# MPB-03a.net
KiCad netlist of a schematic drawn in EAGLE
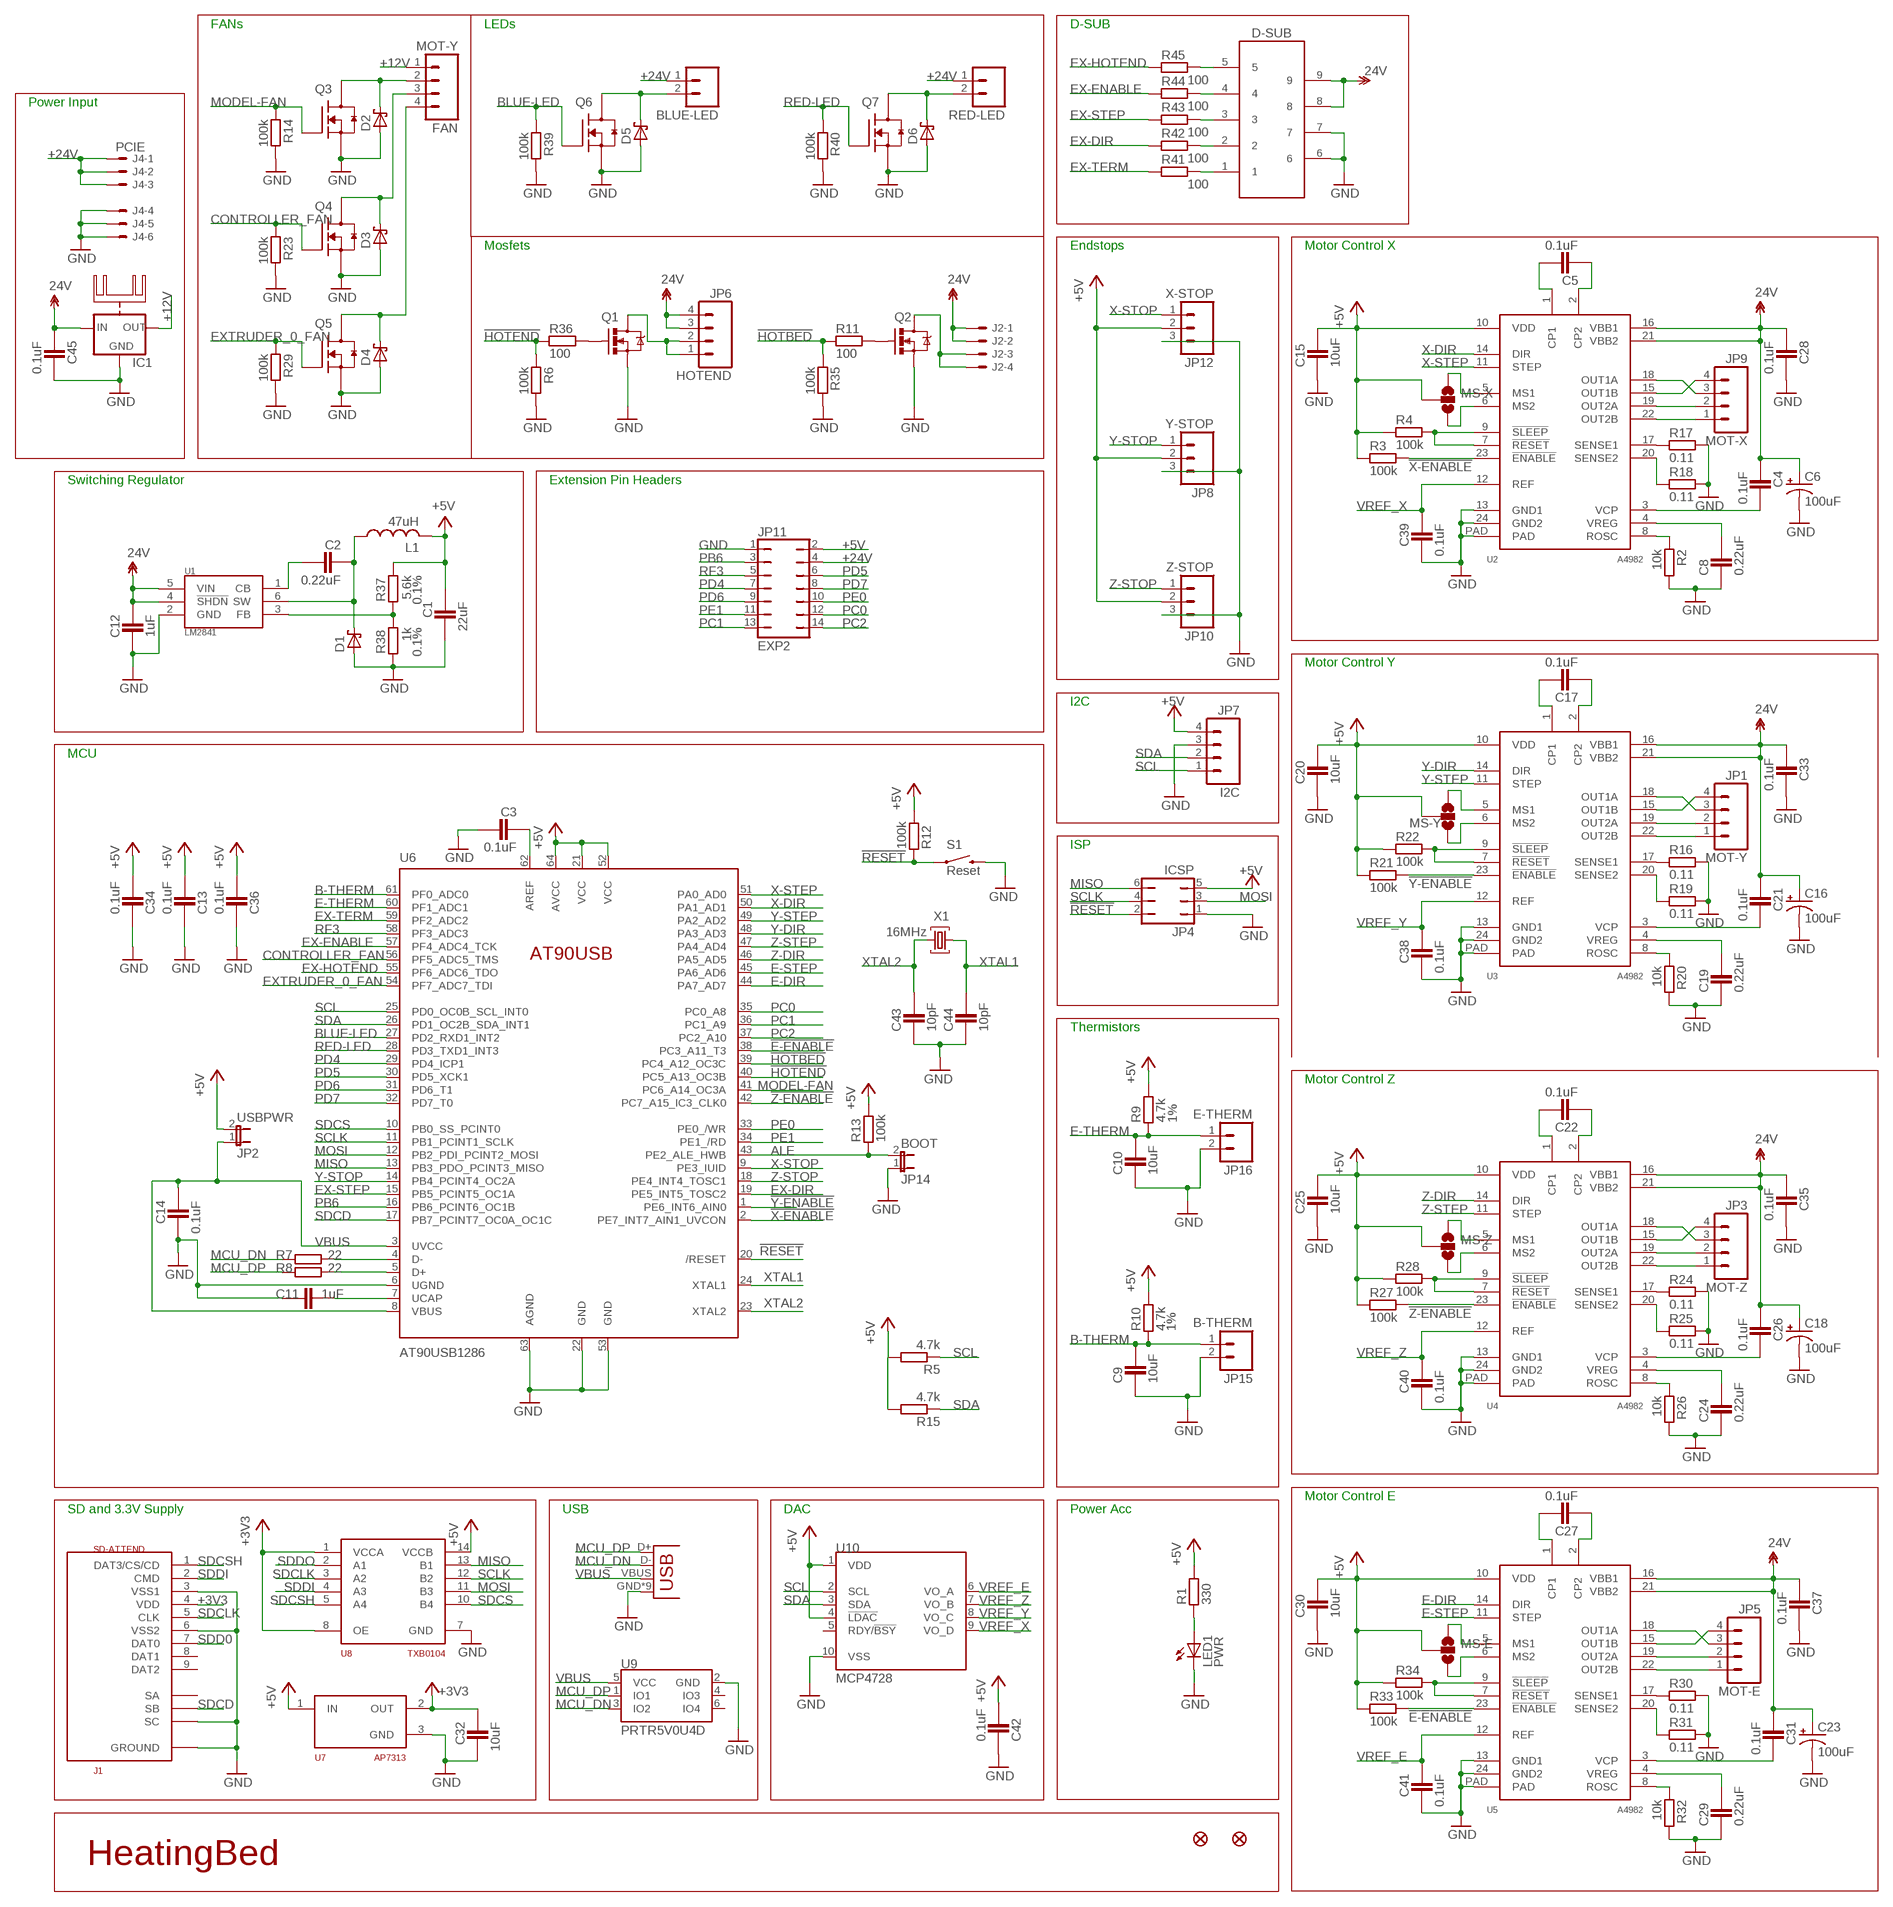
[diagram p0: schematic, sheet 1]

(export (version "E")
  (design (tool "Eeschema 10.0.6"))
  (components
    (comp (ref "BLUE-LED")
      (value "M02POLAR")
      (footprint "eagle-import:MOLEX-1X2")
      (libsource (lib "eagle-import") (part "M02POLAR"))
    )
    (comp (ref "C1")
      (value "22uF")
      (footprint "eagle-import:CAPC2012X145AN")
      (libsource (lib "eagle-import") (part "CAPACITOR_0805"))
    )
    (comp (ref "C2")
      (value "0.22uF")
      (footprint "eagle-import:CAPC2012X145AN")
      (libsource (lib "eagle-import") (part "CAPACITOR_0805"))
    )
    (comp (ref "C3")
      (value "0.1uF")
      (footprint "eagle-import:CAPC2012X145AN")
      (libsource (lib "eagle-import") (part "CAPACITOR_0805"))
    )
    (comp (ref "C4")
      (value "0.1uF")
      (footprint "eagle-import:CAPC2012X145AN")
      (libsource (lib "eagle-import") (part "CAPACITOR_0805"))
    )
    (comp (ref "C5")
      (value "0.1uF")
      (footprint "eagle-import:CAPC2012X145AN")
      (libsource (lib "eagle-import") (part "CAPACITOR_0805"))
    )
    (comp (ref "C6")
      (value "100uF")
      (footprint "eagle-import:PANASONIC_D")
      (libsource (lib "eagle-import") (part "CPOL-USD"))
    )
    (comp (ref "C8")
      (value "0.22uF")
      (footprint "eagle-import:CAPC2012X145AN")
      (libsource (lib "eagle-import") (part "CAPACITOR_0805"))
    )
    (comp (ref "C9")
      (value "10uF")
      (footprint "eagle-import:CAPC2012X145AN")
      (libsource (lib "eagle-import") (part "CAPACITOR_0805"))
    )
    (comp (ref "C10")
      (value "10uF")
      (footprint "eagle-import:CAPC2012X145AN")
      (libsource (lib "eagle-import") (part "CAPACITOR_0805"))
    )
    (comp (ref "C11")
      (value "1uF")
      (footprint "eagle-import:CAPC2012X145AN")
      (libsource (lib "eagle-import") (part "CAPACITOR_0805"))
    )
    (comp (ref "C12")
      (value "1uF")
      (footprint "eagle-import:CAPC2012X145AN")
      (libsource (lib "eagle-import") (part "CAPACITOR_0805"))
    )
    (comp (ref "C13")
      (value "0.1uF")
      (footprint "eagle-import:CAPC2012X145AN")
      (libsource (lib "eagle-import") (part "CAPACITOR_0805"))
    )
    (comp (ref "C14")
      (value "0.1uF")
      (footprint "eagle-import:CAPC2012X145AN")
      (libsource (lib "eagle-import") (part "CAPACITOR_0805"))
    )
    (comp (ref "C15")
      (value "10uF")
      (footprint "eagle-import:CAPC2012X145AN")
      (libsource (lib "eagle-import") (part "CAPACITOR_0805"))
    )
    (comp (ref "C16")
      (value "100uF")
      (footprint "eagle-import:PANASONIC_D")
      (libsource (lib "eagle-import") (part "CPOL-USD"))
    )
    (comp (ref "C17")
      (value "0.1uF")
      (footprint "eagle-import:CAPC2012X145AN")
      (libsource (lib "eagle-import") (part "CAPACITOR_0805"))
    )
    (comp (ref "C18")
      (value "100uF")
      (footprint "eagle-import:PANASONIC_D")
      (libsource (lib "eagle-import") (part "CPOL-USD"))
    )
    (comp (ref "C19")
      (value "0.22uF")
      (footprint "eagle-import:CAPC2012X145AN")
      (libsource (lib "eagle-import") (part "CAPACITOR_0805"))
    )
    (comp (ref "C20")
      (value "10uF")
      (footprint "eagle-import:CAPC2012X145AN")
      (libsource (lib "eagle-import") (part "CAPACITOR_0805"))
    )
    (comp (ref "C21")
      (value "0.1uF")
      (footprint "eagle-import:CAPC2012X145AN")
      (libsource (lib "eagle-import") (part "CAPACITOR_0805"))
    )
    (comp (ref "C22")
      (value "0.1uF")
      (footprint "eagle-import:CAPC2012X145AN")
      (libsource (lib "eagle-import") (part "CAPACITOR_0805"))
    )
    (comp (ref "C23")
      (value "100uF")
      (footprint "eagle-import:PANASONIC_D")
      (libsource (lib "eagle-import") (part "CPOL-USD"))
    )
    (comp (ref "C24")
      (value "0.22uF")
      (footprint "eagle-import:CAPC2012X145AN")
      (libsource (lib "eagle-import") (part "CAPACITOR_0805"))
    )
    (comp (ref "C25")
      (value "10uF")
      (footprint "eagle-import:CAPC2012X145AN")
      (libsource (lib "eagle-import") (part "CAPACITOR_0805"))
    )
    (comp (ref "C26")
      (value "0.1uF")
      (footprint "eagle-import:CAPC2012X145AN")
      (libsource (lib "eagle-import") (part "CAPACITOR_0805"))
    )
    (comp (ref "C27")
      (value "0.1uF")
      (footprint "eagle-import:CAPC2012X145AN")
      (libsource (lib "eagle-import") (part "CAPACITOR_0805"))
    )
    (comp (ref "C28")
      (value "0.1uF")
      (footprint "eagle-import:CAPC2012X145AN")
      (libsource (lib "eagle-import") (part "CAPACITOR_0805"))
    )
    (comp (ref "C29")
      (value "0.22uF")
      (footprint "eagle-import:CAPC2012X145AN")
      (libsource (lib "eagle-import") (part "CAPACITOR_0805"))
    )
    (comp (ref "C30")
      (value "10uF")
      (footprint "eagle-import:CAPC2012X145AN")
      (libsource (lib "eagle-import") (part "CAPACITOR_0805"))
    )
    (comp (ref "C31")
      (value "0.1uF")
      (footprint "eagle-import:CAPC2012X145AN")
      (libsource (lib "eagle-import") (part "CAPACITOR_0805"))
    )
    (comp (ref "C32")
      (value "10uF")
      (footprint "eagle-import:CAPC2012X145AN")
      (libsource (lib "eagle-import") (part "CAPACITOR_0805"))
    )
    (comp (ref "C33")
      (value "0.1uF")
      (footprint "eagle-import:CAPC2012X145AN")
      (libsource (lib "eagle-import") (part "CAPACITOR_0805"))
    )
    (comp (ref "C34")
      (value "0.1uF")
      (footprint "eagle-import:CAPC2012X145AN")
      (libsource (lib "eagle-import") (part "CAPACITOR_0805"))
    )
    (comp (ref "C35")
      (value "0.1uF")
      (footprint "eagle-import:CAPC2012X145AN")
      (libsource (lib "eagle-import") (part "CAPACITOR_0805"))
    )
    (comp (ref "C36")
      (value "0.1uF")
      (footprint "eagle-import:CAPC2012X145AN")
      (libsource (lib "eagle-import") (part "CAPACITOR_0805"))
    )
    (comp (ref "C37")
      (value "0.1uF")
      (footprint "eagle-import:CAPC2012X145AN")
      (libsource (lib "eagle-import") (part "CAPACITOR_0805"))
    )
    (comp (ref "C38")
      (value "0.1uF")
      (footprint "eagle-import:CAPC2012X145AN")
      (libsource (lib "eagle-import") (part "CAPACITOR_0805"))
    )
    (comp (ref "C39")
      (value "0.1uF")
      (footprint "eagle-import:CAPC2012X145AN")
      (libsource (lib "eagle-import") (part "CAPACITOR_0805"))
    )
    (comp (ref "C40")
      (value "0.1uF")
      (footprint "eagle-import:CAPC2012X145AN")
      (libsource (lib "eagle-import") (part "CAPACITOR_0805"))
    )
    (comp (ref "C41")
      (value "0.1uF")
      (footprint "eagle-import:CAPC2012X145AN")
      (libsource (lib "eagle-import") (part "CAPACITOR_0805"))
    )
    (comp (ref "C42")
      (value "0.1uF")
      (footprint "eagle-import:CAPC2012X145AN")
      (libsource (lib "eagle-import") (part "CAPACITOR_0805"))
    )
    (comp (ref "C43")
      (value "10pF")
      (footprint "eagle-import:CAPC2012X145AN")
      (libsource (lib "eagle-import") (part "CAPACITOR_0805"))
    )
    (comp (ref "C44")
      (value "10pF")
      (footprint "eagle-import:CAPC2012X145AN")
      (libsource (lib "eagle-import") (part "CAPACITOR_0805"))
    )
    (comp (ref "C45")
      (value "0.1uF")
      (footprint "eagle-import:CAPC2012X145AN")
      (libsource (lib "eagle-import") (part "CAPACITOR_0805"))
    )
    (comp (ref "D-SUB")
      (value "618009211721")
      (footprint "eagle-import:618009211721")
      (libsource (lib "eagle-import") (part "618009211721"))
    )
    (comp (ref "D1")
      (value "SCH-DIODESMA")
      (footprint "eagle-import:SMA")
      (libsource (lib "eagle-import") (part "SCH-DIODESMA"))
    )
    (comp (ref "D2")
      (value "SCH-DIODESMA")
      (footprint "eagle-import:SMA")
      (libsource (lib "eagle-import") (part "SCH-DIODESMA"))
    )
    (comp (ref "D3")
      (value "SCH-DIODESMA")
      (footprint "eagle-import:SMA")
      (libsource (lib "eagle-import") (part "SCH-DIODESMA"))
    )
    (comp (ref "D4")
      (value "SCH-DIODESMA")
      (footprint "eagle-import:SMA")
      (libsource (lib "eagle-import") (part "SCH-DIODESMA"))
    )
    (comp (ref "D5")
      (value "SCH-DIODESMA")
      (footprint "eagle-import:SMA")
      (libsource (lib "eagle-import") (part "SCH-DIODESMA"))
    )
    (comp (ref "D6")
      (value "SCH-DIODESMA")
      (footprint "eagle-import:SMA")
      (libsource (lib "eagle-import") (part "SCH-DIODESMA"))
    )
    (comp (ref "FAN")
      (value "MOT-Y")
      (footprint "eagle-import:MOLEX-1X4")
      (libsource (lib "eagle-import") (part "M04POLAR"))
    )
    (comp (ref "IC1")
      (value "78XXH")
      (footprint "eagle-import:TO220-15X17X25")
      (libsource (lib "eagle-import") (part "78XXH"))
    )
    (comp (ref "J1")
      (value "SD-ATTEND")
      (footprint "eagle-import:SD-ATTEND")
      (libsource (lib "eagle-import") (part "SD-ATTEND"))
    )
    (comp (ref "J2")
      (value "5566-4")
      (footprint "eagle-import:5566-4")
      (libsource (lib "eagle-import") (part "5566-4"))
    )
    (comp (ref "J3")
      (value "USB-MICRO-PTH")
      (footprint "eagle-import:USB-MICROB-PTH")
      (libsource (lib "eagle-import") (part "USB-MICRO-PTH"))
    )
    (comp (ref "J4")
      (value "PCIE")
      (footprint "eagle-import:5566-6")
      (fields (field (name "MPN") "95566-61002"))
      (libsource (lib "eagle-import") (part "5566-6"))
    )
    (comp (ref "JP1")
      (value "MOT-Y")
      (footprint "eagle-import:MOLEX-1X4")
      (libsource (lib "eagle-import") (part "M04POLAR"))
    )
    (comp (ref "JP2")
      (value "USBPWR")
      (footprint "eagle-import:1X02")
      (libsource (lib "eagle-import") (part "JUMPER-2PTH"))
    )
    (comp (ref "JP3")
      (value "MOT-Z")
      (footprint "eagle-import:MOLEX-1X4")
      (libsource (lib "eagle-import") (part "M04POLAR"))
    )
    (comp (ref "JP4")
      (value "ICSP")
      (footprint "eagle-import:JP3Q")
      (libsource (lib "eagle-import") (part "JP3Q"))
    )
    (comp (ref "JP5")
      (value "MOT-E")
      (footprint "eagle-import:MOLEX-1X4")
      (libsource (lib "eagle-import") (part "M04POLAR"))
    )
    (comp (ref "JP6")
      (value "HOTEND")
      (footprint "eagle-import:MOLEX-1X4")
      (libsource (lib "eagle-import") (part "M04POLAR"))
    )
    (comp (ref "JP7")
      (value "I2C")
      (footprint "eagle-import:MOLEX-1X4")
      (libsource (lib "eagle-import") (part "M04POLAR"))
    )
    (comp (ref "JP8")
      (value "Y-STOP")
      (footprint "eagle-import:MOLEX-1X3")
      (libsource (lib "eagle-import") (part "M03POLAR"))
    )
    (comp (ref "JP9")
      (value "MOT-X")
      (footprint "eagle-import:MOLEX-1X4")
      (libsource (lib "eagle-import") (part "M04POLAR"))
    )
    (comp (ref "JP10")
      (value "Z-STOP")
      (footprint "eagle-import:MOLEX-1X3")
      (libsource (lib "eagle-import") (part "M03POLAR"))
    )
    (comp (ref "JP11")
      (value "EXP2")
      (footprint "eagle-import:JP7Q")
      (libsource (lib "eagle-import") (part "JP7Q"))
    )
    (comp (ref "JP12")
      (value "X-STOP")
      (footprint "eagle-import:MOLEX-1X3")
      (libsource (lib "eagle-import") (part "M03POLAR"))
    )
    (comp (ref "JP14")
      (value "BOOT")
      (footprint "eagle-import:1X02")
      (libsource (lib "eagle-import") (part "JUMPER-2PTH"))
    )
    (comp (ref "JP15")
      (value "B-THERM")
      (footprint "eagle-import:1X02")
      (libsource (lib "eagle-import") (part "M02PTH"))
    )
    (comp (ref "JP16")
      (value "E-THERM")
      (footprint "eagle-import:1X02")
      (libsource (lib "eagle-import") (part "M02PTH"))
    )
    (comp (ref "JP26")
      (value "FIDUCIAL1X2.5")
      (footprint "eagle-import:FIDUCIAL-1X2.5")
      (libsource (lib "eagle-import") (part "FIDUCIAL1X2.5"))
    )
    (comp (ref "JP33")
      (value "FIDUCIAL1X2.5")
      (footprint "eagle-import:FIDUCIAL-1X2.5")
      (libsource (lib "eagle-import") (part "FIDUCIAL1X2.5"))
    )
    (comp (ref "L1")
      (value "47uH")
      (footprint "eagle-import:SDR1006")
      (libsource (lib "eagle-import") (part "L-US"))
    )
    (comp (ref "LED1")
      (value "PWR")
      (footprint "eagle-import:CHIP-LED0805")
      (libsource (lib "eagle-import") (part "LEDCHIP-LED0805"))
    )
    (comp (ref "MS-E")
      (value "SOLDERJUMPER_2WAYCONNECTED")
      (footprint "eagle-import:SJ_3_CONNECTED")
      (libsource (lib "eagle-import") (part "SOLDERJUMPER_2WAYCONNECTED"))
    )
    (comp (ref "MS-X")
      (value "SOLDERJUMPER_2WAYCONNECTED")
      (footprint "eagle-import:SJ_3_CONNECTED")
      (libsource (lib "eagle-import") (part "SOLDERJUMPER_2WAYCONNECTED"))
    )
    (comp (ref "MS-Y")
      (value "SOLDERJUMPER_2WAYCONNECTED")
      (footprint "eagle-import:SJ_3_CONNECTED")
      (libsource (lib "eagle-import") (part "SOLDERJUMPER_2WAYCONNECTED"))
    )
    (comp (ref "MS-Z")
      (value "SOLDERJUMPER_2WAYCONNECTED")
      (footprint "eagle-import:SJ_3_CONNECTED")
      (libsource (lib "eagle-import") (part "SOLDERJUMPER_2WAYCONNECTED"))
    )
    (comp (ref "Q1")
      (value "RFP30N06LE")
      (footprint "eagle-import:TO220V")
      (libsource (lib "eagle-import") (part "MOSFET-NCHANNELPTH2"))
    )
    (comp (ref "Q2")
      (value "RFP30N06LE")
      (footprint "eagle-import:TO220V")
      (libsource (lib "eagle-import") (part "MOSFET-NCHANNELPTH2"))
    )
    (comp (ref "Q3")
      (value "RFP30N06LE")
      (footprint "eagle-import:SOT95P280X135-3N")
      (libsource (lib "eagle-import") (part "MOSFET-NCH_SOT-23"))
    )
    (comp (ref "Q4")
      (value "RFP30N06LE")
      (footprint "eagle-import:SOT95P280X135-3N")
      (libsource (lib "eagle-import") (part "MOSFET-NCH_SOT-23"))
    )
    (comp (ref "Q5")
      (value "RFP30N06LE")
      (footprint "eagle-import:SOT95P280X135-3N")
      (libsource (lib "eagle-import") (part "MOSFET-NCH_SOT-23"))
    )
    (comp (ref "Q6")
      (value "RFP30N06LE")
      (footprint "eagle-import:SOT95P280X135-3N")
      (libsource (lib "eagle-import") (part "MOSFET-NCH_SOT-23"))
    )
    (comp (ref "Q7")
      (value "RFP30N06LE")
      (footprint "eagle-import:SOT95P280X135-3N")
      (libsource (lib "eagle-import") (part "MOSFET-NCH_SOT-23"))
    )
    (comp (ref "R1")
      (value "330")
      (footprint "eagle-import:RESC2012X70N")
      (libsource (lib "eagle-import") (part "RESISTOR_0805"))
    )
    (comp (ref "R2")
      (value "10k")
      (footprint "eagle-import:RESC2012X70N")
      (libsource (lib "eagle-import") (part "RESISTOR_0805"))
    )
    (comp (ref "R3")
      (value "100k")
      (footprint "eagle-import:RESC2012X70N")
      (libsource (lib "eagle-import") (part "RESISTOR_0805"))
    )
    (comp (ref "R4")
      (value "100k")
      (footprint "eagle-import:RESC2012X70N")
      (libsource (lib "eagle-import") (part "RESISTOR_0805"))
    )
    (comp (ref "R5")
      (value "4.7k")
      (footprint "eagle-import:RESC2012X70N")
      (libsource (lib "eagle-import") (part "RESISTOR_0805"))
    )
    (comp (ref "R6")
      (value "100k")
      (footprint "eagle-import:RESC2012X70N")
      (libsource (lib "eagle-import") (part "RESISTOR_0805"))
    )
    (comp (ref "R7")
      (value "22")
      (footprint "eagle-import:RESC2012X70N")
      (libsource (lib "eagle-import") (part "RESISTOR_0805"))
    )
    (comp (ref "R8")
      (value "22")
      (footprint "eagle-import:RESC2012X70N")
      (libsource (lib "eagle-import") (part "RESISTOR_0805"))
    )
    (comp (ref "R9")
      (value "4.7k")
      (footprint "eagle-import:RESC2012X70N")
      (fields (field (name "TOLERANCE") "1%"))
      (libsource (lib "eagle-import") (part "RESISTOR_0805"))
    )
    (comp (ref "R10")
      (value "4.7k")
      (footprint "eagle-import:RESC2012X70N")
      (fields (field (name "TOLERANCE") "1%"))
      (libsource (lib "eagle-import") (part "RESISTOR_0805"))
    )
    (comp (ref "R11")
      (value "100")
      (footprint "eagle-import:RESC2012X70N")
      (libsource (lib "eagle-import") (part "RESISTOR_0805"))
    )
    (comp (ref "R12")
      (value "100k")
      (footprint "eagle-import:RESC2012X70N")
      (libsource (lib "eagle-import") (part "RESISTOR_0805"))
    )
    (comp (ref "R13")
      (value "100k")
      (footprint "eagle-import:RESC2012X70N")
      (libsource (lib "eagle-import") (part "RESISTOR_0805"))
    )
    (comp (ref "R14")
      (value "100k")
      (footprint "eagle-import:RESC2012X70N")
      (libsource (lib "eagle-import") (part "RESISTOR_0805"))
    )
    (comp (ref "R15")
      (value "4.7k")
      (footprint "eagle-import:RESC2012X70N")
      (libsource (lib "eagle-import") (part "RESISTOR_0805"))
    )
    (comp (ref "R16")
      (value "0.11")
      (footprint "eagle-import:RESC2012X70N")
      (libsource (lib "eagle-import") (part "RESISTOR_0805"))
    )
    (comp (ref "R17")
      (value "0.11")
      (footprint "eagle-import:RESC2012X70N")
      (libsource (lib "eagle-import") (part "RESISTOR_0805"))
    )
    (comp (ref "R18")
      (value "0.11")
      (footprint "eagle-import:RESC2012X70N")
      (libsource (lib "eagle-import") (part "RESISTOR_0805"))
    )
    (comp (ref "R19")
      (value "0.11")
      (footprint "eagle-import:RESC2012X70N")
      (libsource (lib "eagle-import") (part "RESISTOR_0805"))
    )
    (comp (ref "R20")
      (value "10k")
      (footprint "eagle-import:RESC2012X70N")
      (libsource (lib "eagle-import") (part "RESISTOR_0805"))
    )
    (comp (ref "R21")
      (value "100k")
      (footprint "eagle-import:RESC2012X70N")
      (libsource (lib "eagle-import") (part "RESISTOR_0805"))
    )
    (comp (ref "R22")
      (value "100k")
      (footprint "eagle-import:RESC2012X70N")
      (libsource (lib "eagle-import") (part "RESISTOR_0805"))
    )
    (comp (ref "R23")
      (value "100k")
      (footprint "eagle-import:RESC2012X70N")
      (libsource (lib "eagle-import") (part "RESISTOR_0805"))
    )
    (comp (ref "R24")
      (value "0.11")
      (footprint "eagle-import:RESC2012X70N")
      (libsource (lib "eagle-import") (part "RESISTOR_0805"))
    )
    (comp (ref "R25")
      (value "0.11")
      (footprint "eagle-import:RESC2012X70N")
      (libsource (lib "eagle-import") (part "RESISTOR_0805"))
    )
    (comp (ref "R26")
      (value "10k")
      (footprint "eagle-import:RESC2012X70N")
      (libsource (lib "eagle-import") (part "RESISTOR_0805"))
    )
    (comp (ref "R27")
      (value "100k")
      (footprint "eagle-import:RESC2012X70N")
      (libsource (lib "eagle-import") (part "RESISTOR_0805"))
    )
    (comp (ref "R28")
      (value "100k")
      (footprint "eagle-import:RESC2012X70N")
      (libsource (lib "eagle-import") (part "RESISTOR_0805"))
    )
    (comp (ref "R29")
      (value "100k")
      (footprint "eagle-import:RESC2012X70N")
      (libsource (lib "eagle-import") (part "RESISTOR_0805"))
    )
    (comp (ref "R30")
      (value "0.11")
      (footprint "eagle-import:RESC2012X70N")
      (libsource (lib "eagle-import") (part "RESISTOR_0805"))
    )
    (comp (ref "R31")
      (value "0.11")
      (footprint "eagle-import:RESC2012X70N")
      (libsource (lib "eagle-import") (part "RESISTOR_0805"))
    )
    (comp (ref "R32")
      (value "10k")
      (footprint "eagle-import:RESC2012X70N")
      (libsource (lib "eagle-import") (part "RESISTOR_0805"))
    )
    (comp (ref "R33")
      (value "100k")
      (footprint "eagle-import:RESC2012X70N")
      (libsource (lib "eagle-import") (part "RESISTOR_0805"))
    )
    (comp (ref "R34")
      (value "100k")
      (footprint "eagle-import:RESC2012X70N")
      (libsource (lib "eagle-import") (part "RESISTOR_0805"))
    )
    (comp (ref "R35")
      (value "100k")
      (footprint "eagle-import:RESC2012X70N")
      (libsource (lib "eagle-import") (part "RESISTOR_0805"))
    )
    (comp (ref "R36")
      (value "100")
      (footprint "eagle-import:RESC2012X70N")
      (libsource (lib "eagle-import") (part "RESISTOR_0805"))
    )
    (comp (ref "R37")
      (value "5.6k")
      (footprint "eagle-import:RESC2012X70N")
      (fields (field (name "TOLERANCE") "0.1%"))
      (libsource (lib "eagle-import") (part "RESISTOR_0805"))
    )
    (comp (ref "R38")
      (value "1k")
      (footprint "eagle-import:RESC2012X70N")
      (fields (field (name "TOLERANCE") "0.1%"))
      (libsource (lib "eagle-import") (part "RESISTOR_0805"))
    )
    (comp (ref "R39")
      (value "100k")
      (footprint "eagle-import:RESC2012X70N")
      (libsource (lib "eagle-import") (part "RESISTOR_0805"))
    )
    (comp (ref "R40")
      (value "100k")
      (footprint "eagle-import:RESC2012X70N")
      (libsource (lib "eagle-import") (part "RESISTOR_0805"))
    )
    (comp (ref "R41")
      (value "100")
      (footprint "eagle-import:RESC2012X70N")
      (libsource (lib "eagle-import") (part "RESISTOR_0805"))
    )
    (comp (ref "R42")
      (value "100")
      (footprint "eagle-import:RESC2012X70N")
      (libsource (lib "eagle-import") (part "RESISTOR_0805"))
    )
    (comp (ref "R43")
      (value "100")
      (footprint "eagle-import:RESC2012X70N")
      (libsource (lib "eagle-import") (part "RESISTOR_0805"))
    )
    (comp (ref "R44")
      (value "100")
      (footprint "eagle-import:RESC2012X70N")
      (libsource (lib "eagle-import") (part "RESISTOR_0805"))
    )
    (comp (ref "R45")
      (value "100")
      (footprint "eagle-import:RESC2012X70N")
      (libsource (lib "eagle-import") (part "RESISTOR_0805"))
    )
    (comp (ref "RED-LED")
      (value "M02POLAR")
      (footprint "eagle-import:MOLEX-1X2")
      (libsource (lib "eagle-import") (part "M02POLAR"))
    )
    (comp (ref "S1")
      (value "Reset")
      (footprint "eagle-import:TACTILE_SWITCH_TALL")
      (libsource (lib "eagle-import") (part "SWITCH-MOMENTARY-2"))
    )
    (comp (ref "U1")
      (value "LM2841")
      (footprint "eagle-import:TSOT6")
      (libsource (lib "eagle-import") (part "LM2841"))
    )
    (comp (ref "U2")
      (value "A4982")
      (footprint "eagle-import:TSSOP-24")
      (libsource (lib "eagle-import") (part "A4982"))
    )
    (comp (ref "U3")
      (value "A4982")
      (footprint "eagle-import:TSSOP-24")
      (libsource (lib "eagle-import") (part "A4982"))
    )
    (comp (ref "U4")
      (value "A4982")
      (footprint "eagle-import:TSSOP-24")
      (libsource (lib "eagle-import") (part "A4982"))
    )
    (comp (ref "U5")
      (value "A4982")
      (footprint "eagle-import:TSSOP-24")
      (libsource (lib "eagle-import") (part "A4982"))
    )
    (comp (ref "U6")
      (value "AT90USB1286")
      (footprint "eagle-import:TQFP64-2")
      (libsource (lib "eagle-import") (part "AT90USB"))
    )
    (comp (ref "U7")
      (value "AP7313")
      (footprint "eagle-import:SOT23C")
      (libsource (lib "eagle-import") (part "AP7313"))
    )
    (comp (ref "U8")
      (value "TXB0104")
      (footprint "eagle-import:TSSOP14")
      (libsource (lib "eagle-import") (part "TXB0104"))
    )
    (comp (ref "U9")
      (value "PRTR5V0U4D")
      (footprint "eagle-import:SOT23-6")
      (libsource (lib "eagle-import") (part "PRTR5V0U4D"))
    )
    (comp (ref "U10")
      (value "MCP4728")
      (footprint "eagle-import:MSOP10")
      (libsource (lib "eagle-import") (part "MCP4728"))
    )
    (comp (ref "X1")
      (value "16MHz")
      (footprint "eagle-import:NDK-XTAL")
      (libsource (lib "eagle-import") (part "XTAL"))
    )
  )
  (nets
    (net (code "1") (name "+3V3") (class "Default")
      (node (ref "C32") (pin "1") (pinfunction "1_1") (pintype "passive"))
      (node (ref "J1") (pin "4") (pinfunction "VDD_4") (pintype "power_in"))
      (node (ref "U7") (pin "2") (pinfunction "OUT_2") (pintype "power_in"))
      (node (ref "U8") (pin "1") (pinfunction "VCCA_1") (pintype "power_in"))
      (node (ref "U8") (pin "8") (pinfunction "OE_8") (pintype "input"))
    )
    (net (code "2") (name "+5V") (class "Default")
      (node (ref "C1") (pin "1") (pinfunction "1_1") (pintype "passive"))
      (node (ref "C13") (pin "2") (pinfunction "2_2") (pintype "passive"))
      (node (ref "C15") (pin "2") (pinfunction "2_2") (pintype "passive"))
      (node (ref "C20") (pin "2") (pinfunction "2_2") (pintype "passive"))
      (node (ref "C25") (pin "2") (pinfunction "2_2") (pintype "passive"))
      (node (ref "C30") (pin "2") (pinfunction "2_2") (pintype "passive"))
      (node (ref "C34") (pin "2") (pinfunction "2_2") (pintype "passive"))
      (node (ref "C36") (pin "2") (pinfunction "2_2") (pintype "passive"))
      (node (ref "C42") (pin "2") (pinfunction "2_2") (pintype "passive"))
      (node (ref "JP10") (pin "2") (pinfunction "2_2") (pintype "passive"))
      (node (ref "JP11") (pin "2") (pinfunction "2_2") (pintype "passive"))
      (node (ref "JP12") (pin "2") (pinfunction "2_2") (pintype "passive"))
      (node (ref "JP2") (pin "2") (pinfunction "2_2") (pintype "passive"))
      (node (ref "JP4") (pin "5") (pinfunction "5_5") (pintype "passive"))
      (node (ref "JP7") (pin "4") (pinfunction "4_4") (pintype "passive"))
      (node (ref "JP8") (pin "2") (pinfunction "2_2") (pintype "passive"))
      (node (ref "L1") (pin "P$2") (pinfunction "2_P$2") (pintype "passive"))
      (node (ref "MS-E") (pin "2") (pinfunction "2_2") (pintype "passive"))
      (node (ref "MS-X") (pin "2") (pinfunction "2_2") (pintype "passive"))
      (node (ref "MS-Y") (pin "2") (pinfunction "2_2") (pintype "passive"))
      (node (ref "MS-Z") (pin "2") (pinfunction "2_2") (pintype "passive"))
      (node (ref "R1") (pin "2") (pinfunction "2_2") (pintype "passive"))
      (node (ref "R10") (pin "2") (pinfunction "2_2") (pintype "passive"))
      (node (ref "R12") (pin "2") (pinfunction "2_2") (pintype "passive"))
      (node (ref "R13") (pin "2") (pinfunction "2_2") (pintype "passive"))
      (node (ref "R15") (pin "2") (pinfunction "2_2") (pintype "passive"))
      (node (ref "R21") (pin "1") (pinfunction "1_1") (pintype "passive"))
      (node (ref "R22") (pin "1") (pinfunction "1_1") (pintype "passive"))
      (node (ref "R27") (pin "1") (pinfunction "1_1") (pintype "passive"))
      (node (ref "R28") (pin "1") (pinfunction "1_1") (pintype "passive"))
      (node (ref "R3") (pin "1") (pinfunction "1_1") (pintype "passive"))
      (node (ref "R33") (pin "1") (pinfunction "1_1") (pintype "passive"))
      (node (ref "R34") (pin "1") (pinfunction "1_1") (pintype "passive"))
      (node (ref "R37") (pin "1") (pinfunction "1_1") (pintype "passive"))
      (node (ref "R4") (pin "1") (pinfunction "1_1") (pintype "passive"))
      (node (ref "R5") (pin "2") (pinfunction "2_2") (pintype "passive"))
      (node (ref "R9") (pin "2") (pinfunction "2_2") (pintype "passive"))
      (node (ref "U10") (pin "1") (pinfunction "VDD_1") (pintype "power_in"))
      (node (ref "U10") (pin "4") (pinfunction "~{LDAC}_4") (pintype "input"))
      (node (ref "U2") (pin "10") (pinfunction "VDD_10") (pintype "power_in"))
      (node (ref "U3") (pin "10") (pinfunction "VDD_10") (pintype "power_in"))
      (node (ref "U4") (pin "10") (pinfunction "VDD_10") (pintype "power_in"))
      (node (ref "U5") (pin "10") (pinfunction "VDD_10") (pintype "power_in"))
      (node (ref "U6") (pin "21") (pinfunction "VCC_21") (pintype "power_in"))
      (node (ref "U6") (pin "52") (pinfunction "VCC_52") (pintype "power_in"))
      (node (ref "U6") (pin "64") (pinfunction "AVCC_64") (pintype "power_in"))
      (node (ref "U7") (pin "1") (pinfunction "IN_1") (pintype "power_in"))
      (node (ref "U8") (pin "14") (pinfunction "VCCB_14") (pintype "power_in"))
    )
    (net (code "3") (name "/+12V") (class "Default")
      (node (ref "FAN") (pin "1") (pinfunction "1_1") (pintype "passive"))
      (node (ref "IC1") (pin "OUT") (pinfunction "OUT_OUT") (pintype "passive"))
    )
    (net (code "4") (name "/ALE") (class "Default")
      (node (ref "JP14") (pin "2") (pinfunction "2_2") (pintype "passive"))
      (node (ref "R13") (pin "1") (pinfunction "1_1") (pintype "passive"))
      (node (ref "U6") (pin "43") (pinfunction "PE2_ALE_HWB_43") (pintype "bidirectional"))
    )
    (net (code "5") (name "/B-THERM") (class "Default")
      (node (ref "C9") (pin "2") (pinfunction "2_2") (pintype "passive"))
      (node (ref "JP15") (pin "1") (pinfunction "1_1") (pintype "passive"))
      (node (ref "R10") (pin "1") (pinfunction "1_1") (pintype "passive"))
      (node (ref "U6") (pin "61") (pinfunction "PF0_ADC0_61") (pintype "bidirectional"))
    )
    (net (code "6") (name "/BLUE-LED") (class "Default")
      (node (ref "Q6") (pin "1") (pinfunction "G_1") (pintype "passive"))
      (node (ref "R39") (pin "1") (pinfunction "1_1") (pintype "passive"))
      (node (ref "U6") (pin "27") (pinfunction "PD2_RXD1_INT2_27") (pintype "bidirectional"))
    )
    (net (code "7") (name "/CONTROLLER_FAN") (class "Default")
      (node (ref "Q4") (pin "1") (pinfunction "G_1") (pintype "passive"))
      (node (ref "R23") (pin "1") (pinfunction "1_1") (pintype "passive"))
      (node (ref "U6") (pin "56") (pinfunction "PF5_ADC5_TMS_56") (pintype "bidirectional"))
    )
    (net (code "8") (name "/E-DIR") (class "Default")
      (node (ref "U5") (pin "14") (pinfunction "DIR_14") (pintype "input"))
      (node (ref "U6") (pin "44") (pinfunction "PA7_AD7_44") (pintype "bidirectional"))
    )
    (net (code "9") (name "/E-STEP") (class "Default")
      (node (ref "U5") (pin "11") (pinfunction "STEP_11") (pintype "input"))
      (node (ref "U6") (pin "45") (pinfunction "PA6_AD6_45") (pintype "bidirectional"))
    )
    (net (code "10") (name "/E-THERM") (class "Default")
      (node (ref "C10") (pin "2") (pinfunction "2_2") (pintype "passive"))
      (node (ref "JP16") (pin "1") (pinfunction "1_1") (pintype "passive"))
      (node (ref "R9") (pin "1") (pinfunction "1_1") (pintype "passive"))
      (node (ref "U6") (pin "60") (pinfunction "PF1_ADC1_60") (pintype "bidirectional"))
    )
    (net (code "11") (name "/EX-DIR") (class "Default")
      (node (ref "R42") (pin "1") (pinfunction "1_1") (pintype "passive"))
      (node (ref "U6") (pin "19") (pinfunction "PE5_INT5_TOSC2_19") (pintype "bidirectional"))
    )
    (net (code "12") (name "/EX-ENABLE") (class "Default")
      (node (ref "R44") (pin "1") (pinfunction "1_1") (pintype "passive"))
      (node (ref "U6") (pin "57") (pinfunction "PF4_ADC4_TCK_57") (pintype "bidirectional"))
    )
    (net (code "13") (name "/EX-HOTEND") (class "Default")
      (node (ref "R45") (pin "1") (pinfunction "1_1") (pintype "passive"))
      (node (ref "U6") (pin "55") (pinfunction "PF6_ADC6_TDO_55") (pintype "bidirectional"))
    )
    (net (code "14") (name "/EX-STEP") (class "Default")
      (node (ref "R43") (pin "1") (pinfunction "1_1") (pintype "passive"))
      (node (ref "U6") (pin "15") (pinfunction "PB5_PCINT5_OC1A_15") (pintype "bidirectional"))
    )
    (net (code "15") (name "/EX-TERM") (class "Default")
      (node (ref "R41") (pin "1") (pinfunction "1_1") (pintype "passive"))
      (node (ref "U6") (pin "59") (pinfunction "PF2_ADC2_59") (pintype "bidirectional"))
    )
    (net (code "16") (name "/EXTRUDER_0_FAN") (class "Default")
      (node (ref "Q5") (pin "1") (pinfunction "G_1") (pintype "passive"))
      (node (ref "R29") (pin "1") (pinfunction "1_1") (pintype "passive"))
      (node (ref "U6") (pin "54") (pinfunction "PF7_ADC7_TDI_54") (pintype "bidirectional"))
    )
    (net (code "17") (name "/MCU_DN") (class "Default")
      (node (ref "J3") (pin "D-") (pinfunction "D-_D-") (pintype "bidirectional"))
      (node (ref "R7") (pin "1") (pinfunction "1_1") (pintype "passive"))
      (node (ref "U9") (pin "3") (pinfunction "IO2_3") (pintype "bidirectional"))
    )
    (net (code "18") (name "/MCU_DP") (class "Default")
      (node (ref "J3") (pin "D+") (pinfunction "D+_D+") (pintype "bidirectional"))
      (node (ref "R8") (pin "1") (pinfunction "1_1") (pintype "passive"))
      (node (ref "U9") (pin "1") (pinfunction "IO1_1") (pintype "bidirectional"))
    )
    (net (code "19") (name "/MISO") (class "Default")
      (node (ref "JP4") (pin "6") (pinfunction "6_6") (pintype "passive"))
      (node (ref "U6") (pin "13") (pinfunction "PB3_PDO_PCINT3_MISO_13") (pintype "bidirectional"))
      (node (ref "U8") (pin "13") (pinfunction "B1_13") (pintype "bidirectional"))
    )
    (net (code "20") (name "/MODEL-FAN") (class "Default")
      (node (ref "Q3") (pin "1") (pinfunction "G_1") (pintype "passive"))
      (node (ref "R14") (pin "1") (pinfunction "1_1") (pintype "passive"))
      (node (ref "U6") (pin "41") (pinfunction "PC6_A14_OC3A_41") (pintype "bidirectional"))
    )
    (net (code "21") (name "/MOSI") (class "Default")
      (node (ref "JP4") (pin "3") (pinfunction "3_3") (pintype "passive"))
      (node (ref "U6") (pin "12") (pinfunction "PB2_PDI_PCINT2_MOSI_12") (pintype "bidirectional"))
      (node (ref "U8") (pin "11") (pinfunction "B3_11") (pintype "bidirectional"))
    )
    (net (code "22") (name "/PB6") (class "Default")
      (node (ref "JP11") (pin "3") (pinfunction "3_3") (pintype "passive"))
      (node (ref "U6") (pin "16") (pinfunction "PB6_PCINT6_OC1B_16") (pintype "bidirectional"))
    )
    (net (code "23") (name "/PC0") (class "Default")
      (node (ref "JP11") (pin "12") (pinfunction "12_12") (pintype "passive"))
      (node (ref "U6") (pin "35") (pinfunction "PC0_A8_35") (pintype "bidirectional"))
    )
    (net (code "24") (name "/PC1") (class "Default")
      (node (ref "JP11") (pin "13") (pinfunction "13_13") (pintype "passive"))
      (node (ref "U6") (pin "36") (pinfunction "PC1_A9_36") (pintype "bidirectional"))
    )
    (net (code "25") (name "/PC2") (class "Default")
      (node (ref "JP11") (pin "14") (pinfunction "14_14") (pintype "passive"))
      (node (ref "U6") (pin "37") (pinfunction "PC2_A10_37") (pintype "bidirectional"))
    )
    (net (code "26") (name "/PD4") (class "Default")
      (node (ref "JP11") (pin "7") (pinfunction "7_7") (pintype "passive"))
      (node (ref "U6") (pin "29") (pinfunction "PD4_ICP1_29") (pintype "bidirectional"))
    )
    (net (code "27") (name "/PD5") (class "Default")
      (node (ref "JP11") (pin "6") (pinfunction "6_6") (pintype "passive"))
      (node (ref "U6") (pin "30") (pinfunction "PD5_XCK1_30") (pintype "bidirectional"))
    )
    (net (code "28") (name "/PD6") (class "Default")
      (node (ref "JP11") (pin "9") (pinfunction "9_9") (pintype "passive"))
      (node (ref "U6") (pin "31") (pinfunction "PD6_T1_31") (pintype "bidirectional"))
    )
    (net (code "29") (name "/PD7") (class "Default")
      (node (ref "JP11") (pin "8") (pinfunction "8_8") (pintype "passive"))
      (node (ref "U6") (pin "32") (pinfunction "PD7_T0_32") (pintype "bidirectional"))
    )
    (net (code "30") (name "/PE0") (class "Default")
      (node (ref "JP11") (pin "10") (pinfunction "10_10") (pintype "passive"))
      (node (ref "U6") (pin "33") (pinfunction "PE0_/WR_33") (pintype "bidirectional"))
    )
    (net (code "31") (name "/PE1") (class "Default")
      (node (ref "JP11") (pin "11") (pinfunction "11_11") (pintype "passive"))
      (node (ref "U6") (pin "34") (pinfunction "PE1_/RD_34") (pintype "bidirectional"))
    )
    (net (code "32") (name "/RED-LED") (class "Default")
      (node (ref "Q7") (pin "1") (pinfunction "G_1") (pintype "passive"))
      (node (ref "R40") (pin "1") (pinfunction "1_1") (pintype "passive"))
      (node (ref "U6") (pin "28") (pinfunction "PD3_TXD1_INT3_28") (pintype "bidirectional"))
    )
    (net (code "33") (name "/RF3") (class "Default")
      (node (ref "JP11") (pin "5") (pinfunction "5_5") (pintype "passive"))
      (node (ref "U6") (pin "58") (pinfunction "PF3_ADC3_58") (pintype "bidirectional"))
    )
    (net (code "34") (name "/SCL") (class "Default")
      (node (ref "JP7") (pin "1") (pinfunction "1_1") (pintype "passive"))
      (node (ref "R5") (pin "1") (pinfunction "1_1") (pintype "passive"))
      (node (ref "U10") (pin "2") (pinfunction "SCL_2") (pintype "input"))
      (node (ref "U6") (pin "25") (pinfunction "PD0_OC0B_SCL_INT0_25") (pintype "bidirectional"))
    )
    (net (code "35") (name "/SCLK") (class "Default")
      (node (ref "JP4") (pin "4") (pinfunction "4_4") (pintype "passive"))
      (node (ref "U6") (pin "11") (pinfunction "PB1_PCINT1_SCLK_11") (pintype "bidirectional"))
      (node (ref "U8") (pin "12") (pinfunction "B2_12") (pintype "bidirectional"))
    )
    (net (code "36") (name "/SDA") (class "Default")
      (node (ref "JP7") (pin "2") (pinfunction "2_2") (pintype "passive"))
      (node (ref "R15") (pin "1") (pinfunction "1_1") (pintype "passive"))
      (node (ref "U10") (pin "3") (pinfunction "SDA_3") (pintype "bidirectional"))
      (node (ref "U6") (pin "26") (pinfunction "PD1_OC2B_SDA_INT1_26") (pintype "bidirectional"))
    )
    (net (code "37") (name "/SDCD") (class "Default")
      (node (ref "J1") (pin "SB") (pinfunction "SB_SB") (pintype "bidirectional"))
      (node (ref "U6") (pin "17") (pinfunction "PB7_PCINT7_OC0A_OC1C_17") (pintype "bidirectional"))
    )
    (net (code "38") (name "/SDCLK") (class "Default")
      (node (ref "J1") (pin "5") (pinfunction "CLK_5") (pintype "input"))
      (node (ref "U8") (pin "3") (pinfunction "A2_3") (pintype "bidirectional"))
    )
    (net (code "39") (name "/SDCS") (class "Default")
      (node (ref "U6") (pin "10") (pinfunction "PB0_SS_PCINT0_10") (pintype "bidirectional"))
      (node (ref "U8") (pin "10") (pinfunction "B4_10") (pintype "bidirectional"))
    )
    (net (code "40") (name "/SDCSH") (class "Default")
      (node (ref "J1") (pin "1") (pinfunction "DAT3/CS/CD_1") (pintype "bidirectional"))
      (node (ref "U8") (pin "5") (pinfunction "A4_5") (pintype "bidirectional"))
    )
    (net (code "41") (name "/SDD0") (class "Default")
      (node (ref "J1") (pin "7") (pinfunction "DAT0_7") (pintype "bidirectional"))
    )
    (net (code "42") (name "/SDDI") (class "Default")
      (node (ref "J1") (pin "2") (pinfunction "CMD_2") (pintype "bidirectional"))
      (node (ref "U8") (pin "4") (pinfunction "A3_4") (pintype "bidirectional"))
    )
    (net (code "43") (name "/SDDO") (class "Default")
      (node (ref "U8") (pin "2") (pinfunction "A1_2") (pintype "bidirectional"))
    )
    (net (code "44") (name "/VBUS") (class "Default")
      (node (ref "C14") (pin "1") (pinfunction "1_1") (pintype "passive"))
      (node (ref "J3") (pin "VBUS") (pinfunction "VBUS_VBUS") (pintype "bidirectional"))
      (node (ref "JP2") (pin "1") (pinfunction "1_1") (pintype "passive"))
      (node (ref "U6") (pin "3") (pinfunction "UVCC_3") (pintype "power_in"))
      (node (ref "U6") (pin "8") (pinfunction "VBUS_8") (pintype "bidirectional"))
      (node (ref "U9") (pin "5") (pinfunction "VCC_5") (pintype "power_in"))
    )
    (net (code "45") (name "/VREF_E") (class "Default")
      (node (ref "C41") (pin "1") (pinfunction "1_1") (pintype "passive"))
      (node (ref "U10") (pin "6") (pinfunction "VO_A_6") (pintype "output"))
      (node (ref "U5") (pin "12") (pinfunction "REF_12") (pintype "input"))
    )
    (net (code "46") (name "/VREF_X") (class "Default")
      (node (ref "C39") (pin "1") (pinfunction "1_1") (pintype "passive"))
      (node (ref "U10") (pin "9") (pinfunction "VO_D_9") (pintype "output"))
      (node (ref "U2") (pin "12") (pinfunction "REF_12") (pintype "input"))
    )
    (net (code "47") (name "/VREF_Y") (class "Default")
      (node (ref "C38") (pin "1") (pinfunction "1_1") (pintype "passive"))
      (node (ref "U10") (pin "8") (pinfunction "VO_C_8") (pintype "output"))
      (node (ref "U3") (pin "12") (pinfunction "REF_12") (pintype "input"))
    )
    (net (code "48") (name "/VREF_Z") (class "Default")
      (node (ref "C40") (pin "1") (pinfunction "1_1") (pintype "passive"))
      (node (ref "U10") (pin "7") (pinfunction "VO_B_7") (pintype "output"))
      (node (ref "U4") (pin "12") (pinfunction "REF_12") (pintype "input"))
    )
    (net (code "49") (name "/X-DIR") (class "Default")
      (node (ref "U2") (pin "14") (pinfunction "DIR_14") (pintype "input"))
      (node (ref "U6") (pin "50") (pinfunction "PA1_AD1_50") (pintype "bidirectional"))
    )
    (net (code "50") (name "/X-STEP") (class "Default")
      (node (ref "U2") (pin "11") (pinfunction "STEP_11") (pintype "input"))
      (node (ref "U6") (pin "51") (pinfunction "PA0_AD0_51") (pintype "bidirectional"))
    )
    (net (code "51") (name "/X-STOP") (class "Default")
      (node (ref "JP12") (pin "1") (pinfunction "1_1") (pintype "passive"))
      (node (ref "U6") (pin "9") (pinfunction "PE3_IUID_9") (pintype "bidirectional"))
    )
    (net (code "52") (name "/XTAL1") (class "Default")
      (node (ref "C44") (pin "2") (pinfunction "2_2") (pintype "passive"))
      (node (ref "U6") (pin "24") (pinfunction "XTAL1_24") (pintype "passive"))
      (node (ref "X1") (pin "P$1") (pinfunction "1_P$1") (pintype "passive"))
    )
    (net (code "53") (name "/XTAL2") (class "Default")
      (node (ref "C43") (pin "2") (pinfunction "2_2") (pintype "passive"))
      (node (ref "U6") (pin "23") (pinfunction "XTAL2_23") (pintype "passive"))
      (node (ref "X1") (pin "P$2") (pinfunction "2_P$2") (pintype "passive"))
    )
    (net (code "54") (name "/Y-DIR") (class "Default")
      (node (ref "U3") (pin "14") (pinfunction "DIR_14") (pintype "input"))
      (node (ref "U6") (pin "48") (pinfunction "PA3_AD3_48") (pintype "bidirectional"))
    )
    (net (code "55") (name "/Y-STEP") (class "Default")
      (node (ref "U3") (pin "11") (pinfunction "STEP_11") (pintype "input"))
      (node (ref "U6") (pin "49") (pinfunction "PA2_AD2_49") (pintype "bidirectional"))
    )
    (net (code "56") (name "/Y-STOP") (class "Default")
      (node (ref "JP8") (pin "1") (pinfunction "1_1") (pintype "passive"))
      (node (ref "U6") (pin "14") (pinfunction "PB4_PCINT4_OC2A_14") (pintype "bidirectional"))
    )
    (net (code "57") (name "/Z-DIR") (class "Default")
      (node (ref "U4") (pin "14") (pinfunction "DIR_14") (pintype "input"))
      (node (ref "U6") (pin "46") (pinfunction "PA5_AD5_46") (pintype "bidirectional"))
    )
    (net (code "58") (name "/Z-STEP") (class "Default")
      (node (ref "U4") (pin "11") (pinfunction "STEP_11") (pintype "input"))
      (node (ref "U6") (pin "47") (pinfunction "PA4_AD4_47") (pintype "bidirectional"))
    )
    (net (code "59") (name "/Z-STOP") (class "Default")
      (node (ref "JP10") (pin "1") (pinfunction "1_1") (pintype "passive"))
      (node (ref "U6") (pin "18") (pinfunction "PE4_INT4_TOSC1_18") (pintype "bidirectional"))
    )
    (net (code "60") (name "/~{E-ENABLE}") (class "Default")
      (node (ref "R33") (pin "2") (pinfunction "2_2") (pintype "passive"))
      (node (ref "U5") (pin "23") (pinfunction "~{ENABLE}_23") (pintype "input"))
      (node (ref "U6") (pin "38") (pinfunction "PC3_A11_T3_38") (pintype "bidirectional"))
    )
    (net (code "61") (name "/~{HOTBED}") (class "Default")
      (node (ref "R11") (pin "1") (pinfunction "1_1") (pintype "passive"))
      (node (ref "R35") (pin "1") (pinfunction "1_1") (pintype "passive"))
      (node (ref "U6") (pin "39") (pinfunction "PC4_A12_OC3C_39") (pintype "bidirectional"))
    )
    (net (code "62") (name "/~{HOTEND}") (class "Default")
      (node (ref "R36") (pin "1") (pinfunction "1_1") (pintype "passive"))
      (node (ref "R6") (pin "1") (pinfunction "1_1") (pintype "passive"))
      (node (ref "U6") (pin "40") (pinfunction "PC5_A13_OC3B_40") (pintype "bidirectional"))
    )
    (net (code "63") (name "/~{RESET}") (class "Default")
      (node (ref "JP4") (pin "2") (pinfunction "2_2") (pintype "passive"))
      (node (ref "R12") (pin "1") (pinfunction "1_1") (pintype "passive"))
      (node (ref "S1") (pin "A2") (pinfunction "1_A2") (pintype "passive"))
      (node (ref "U6") (pin "20") (pinfunction "/RESET_20") (pintype "bidirectional"))
    )
    (net (code "64") (name "/~{X-ENABLE}") (class "Default")
      (node (ref "R3") (pin "2") (pinfunction "2_2") (pintype "passive"))
      (node (ref "U2") (pin "23") (pinfunction "~{ENABLE}_23") (pintype "input"))
      (node (ref "U6") (pin "2") (pinfunction "PE7_INT7_AIN1_UVCON_2") (pintype "bidirectional"))
    )
    (net (code "65") (name "/~{Y-ENABLE}") (class "Default")
      (node (ref "R21") (pin "2") (pinfunction "2_2") (pintype "passive"))
      (node (ref "U3") (pin "23") (pinfunction "~{ENABLE}_23") (pintype "input"))
      (node (ref "U6") (pin "1") (pinfunction "PE6_INT6_AIN0_1") (pintype "bidirectional"))
    )
    (net (code "66") (name "/~{Z-ENABLE}") (class "Default")
      (node (ref "R27") (pin "2") (pinfunction "2_2") (pintype "passive"))
      (node (ref "U4") (pin "23") (pinfunction "~{ENABLE}_23") (pintype "input"))
      (node (ref "U6") (pin "42") (pinfunction "PC7_A15_IC3_CLK0_42") (pintype "bidirectional"))
    )
    (net (code "67") (name "24V") (class "Default")
      (node (ref "BLUE-LED") (pin "1") (pinfunction "1_1") (pintype "passive"))
      (node (ref "C12") (pin "1") (pinfunction "1_1") (pintype "passive"))
      (node (ref "C16") (pin "+") (pinfunction "+_+") (pintype "passive"))
      (node (ref "C18") (pin "+") (pinfunction "+_+") (pintype "passive"))
      (node (ref "C21") (pin "1") (pinfunction "1_1") (pintype "passive"))
      (node (ref "C23") (pin "+") (pinfunction "+_+") (pintype "passive"))
      (node (ref "C26") (pin "1") (pinfunction "1_1") (pintype "passive"))
      (node (ref "C28") (pin "1") (pinfunction "1_1") (pintype "passive"))
      (node (ref "C31") (pin "1") (pinfunction "1_1") (pintype "passive"))
      (node (ref "C33") (pin "1") (pinfunction "1_1") (pintype "passive"))
      (node (ref "C35") (pin "1") (pinfunction "1_1") (pintype "passive"))
      (node (ref "C37") (pin "1") (pinfunction "1_1") (pintype "passive"))
      (node (ref "C4") (pin "1") (pinfunction "1_1") (pintype "passive"))
      (node (ref "C45") (pin "1") (pinfunction "1_1") (pintype "passive"))
      (node (ref "C6") (pin "+") (pinfunction "+_+") (pintype "passive"))
      (node (ref "D-SUB") (pin "8") (pinfunction "8_8") (pintype "bidirectional"))
      (node (ref "D-SUB") (pin "9") (pinfunction "9_9") (pintype "bidirectional"))
      (node (ref "IC1") (pin "IN") (pinfunction "IN_IN") (pintype "input"))
      (node (ref "J2") (pin "1") (pinfunction "S_1") (pintype "passive"))
      (node (ref "J2") (pin "2") (pinfunction "S_2") (pintype "passive"))
      (node (ref "J4") (pin "1") (pinfunction "S_1") (pintype "passive"))
      (node (ref "J4") (pin "2") (pinfunction "S_2") (pintype "passive"))
      (node (ref "J4") (pin "3") (pinfunction "S_3") (pintype "passive"))
      (node (ref "JP11") (pin "4") (pinfunction "4_4") (pintype "passive"))
      (node (ref "JP6") (pin "3") (pinfunction "3_3") (pintype "passive"))
      (node (ref "JP6") (pin "4") (pinfunction "4_4") (pintype "passive"))
      (node (ref "RED-LED") (pin "1") (pinfunction "1_1") (pintype "passive"))
      (node (ref "U1") (pin "4") (pinfunction "~{SHDN}_4") (pintype "input"))
      (node (ref "U1") (pin "5") (pinfunction "VIN_5") (pintype "power_in"))
      (node (ref "U2") (pin "16") (pinfunction "VBB1_16") (pintype "power_in"))
      (node (ref "U2") (pin "21") (pinfunction "VBB2_21") (pintype "power_in"))
      (node (ref "U3") (pin "16") (pinfunction "VBB1_16") (pintype "power_in"))
      (node (ref "U3") (pin "21") (pinfunction "VBB2_21") (pintype "power_in"))
      (node (ref "U4") (pin "16") (pinfunction "VBB1_16") (pintype "power_in"))
      (node (ref "U4") (pin "21") (pinfunction "VBB2_21") (pintype "power_in"))
      (node (ref "U5") (pin "16") (pinfunction "VBB1_16") (pintype "power_in"))
      (node (ref "U5") (pin "21") (pinfunction "VBB2_21") (pintype "power_in"))
    )
    (net (code "68") (name "GND") (class "Default")
      (node (ref "C1") (pin "2") (pinfunction "2_2") (pintype "passive"))
      (node (ref "C10") (pin "1") (pinfunction "1_1") (pintype "passive"))
      (node (ref "C11") (pin "1") (pinfunction "1_1") (pintype "passive"))
      (node (ref "C12") (pin "2") (pinfunction "2_2") (pintype "passive"))
      (node (ref "C13") (pin "1") (pinfunction "1_1") (pintype "passive"))
      (node (ref "C14") (pin "2") (pinfunction "2_2") (pintype "passive"))
      (node (ref "C15") (pin "1") (pinfunction "1_1") (pintype "passive"))
      (node (ref "C16") (pin "-") (pinfunction "-_-") (pintype "passive"))
      (node (ref "C18") (pin "-") (pinfunction "-_-") (pintype "passive"))
      (node (ref "C19") (pin "1") (pinfunction "1_1") (pintype "passive"))
      (node (ref "C20") (pin "1") (pinfunction "1_1") (pintype "passive"))
      (node (ref "C23") (pin "-") (pinfunction "-_-") (pintype "passive"))
      (node (ref "C24") (pin "1") (pinfunction "1_1") (pintype "passive"))
      (node (ref "C25") (pin "1") (pinfunction "1_1") (pintype "passive"))
      (node (ref "C28") (pin "2") (pinfunction "2_2") (pintype "passive"))
      (node (ref "C29") (pin "1") (pinfunction "1_1") (pintype "passive"))
      (node (ref "C3") (pin "2") (pinfunction "2_2") (pintype "passive"))
      (node (ref "C30") (pin "1") (pinfunction "1_1") (pintype "passive"))
      (node (ref "C32") (pin "2") (pinfunction "2_2") (pintype "passive"))
      (node (ref "C33") (pin "2") (pinfunction "2_2") (pintype "passive"))
      (node (ref "C34") (pin "1") (pinfunction "1_1") (pintype "passive"))
      (node (ref "C35") (pin "2") (pinfunction "2_2") (pintype "passive"))
      (node (ref "C36") (pin "1") (pinfunction "1_1") (pintype "passive"))
      (node (ref "C37") (pin "2") (pinfunction "2_2") (pintype "passive"))
      (node (ref "C38") (pin "2") (pinfunction "2_2") (pintype "passive"))
      (node (ref "C39") (pin "2") (pinfunction "2_2") (pintype "passive"))
      (node (ref "C40") (pin "2") (pinfunction "2_2") (pintype "passive"))
      (node (ref "C41") (pin "2") (pinfunction "2_2") (pintype "passive"))
      (node (ref "C42") (pin "1") (pinfunction "1_1") (pintype "passive"))
      (node (ref "C43") (pin "1") (pinfunction "1_1") (pintype "passive"))
      (node (ref "C44") (pin "1") (pinfunction "1_1") (pintype "passive"))
      (node (ref "C45") (pin "2") (pinfunction "2_2") (pintype "passive"))
      (node (ref "C6") (pin "-") (pinfunction "-_-") (pintype "passive"))
      (node (ref "C8") (pin "1") (pinfunction "1_1") (pintype "passive"))
      (node (ref "C9") (pin "1") (pinfunction "1_1") (pintype "passive"))
      (node (ref "D-SUB") (pin "6") (pinfunction "6_6") (pintype "bidirectional"))
      (node (ref "D-SUB") (pin "7") (pinfunction "7_7") (pintype "bidirectional"))
      (node (ref "D1") (pin "A") (pinfunction "A_A") (pintype "passive"))
      (node (ref "D2") (pin "A") (pinfunction "A_A") (pintype "passive"))
      (node (ref "D3") (pin "A") (pinfunction "A_A") (pintype "passive"))
      (node (ref "D4") (pin "A") (pinfunction "A_A") (pintype "passive"))
      (node (ref "D5") (pin "A") (pinfunction "A_A") (pintype "passive"))
      (node (ref "D6") (pin "A") (pinfunction "A_A") (pintype "passive"))
      (node (ref "IC1") (pin "GND") (pinfunction "GND_GND") (pintype "input"))
      (node (ref "J1") (pin "3") (pinfunction "VSS1_3") (pintype "input"))
      (node (ref "J1") (pin "6") (pinfunction "VSS2_6") (pintype "power_in"))
      (node (ref "J1") (pin "G") (pinfunction "GROUND_G") (pintype "bidirectional"))
      (node (ref "J1") (pin "SC") (pinfunction "SC_SC") (pintype "bidirectional"))
      (node (ref "J3") (pin "GND") (pinfunction "GND_GND") (pintype "bidirectional"))
      (node (ref "J3") (pin "GND1") (pinfunction "GND_GND1") (pintype "bidirectional"))
      (node (ref "J3") (pin "GND2") (pinfunction "GND_GND2") (pintype "bidirectional"))
      (node (ref "J3") (pin "GND3") (pinfunction "GND_GND3") (pintype "bidirectional"))
      (node (ref "J3") (pin "GND4") (pinfunction "GND_GND4") (pintype "bidirectional"))
      (node (ref "J3") (pin "GND5") (pinfunction "GND_GND5") (pintype "bidirectional"))
      (node (ref "J3") (pin "GND6") (pinfunction "GND_GND6") (pintype "bidirectional"))
      (node (ref "J3") (pin "GND7") (pinfunction "GND_GND7") (pintype "bidirectional"))
      (node (ref "J3") (pin "GND8") (pinfunction "GND_GND8") (pintype "bidirectional"))
      (node (ref "J4") (pin "4") (pinfunction "S_4") (pintype "passive"))
      (node (ref "J4") (pin "5") (pinfunction "S_5") (pintype "passive"))
      (node (ref "J4") (pin "6") (pinfunction "S_6") (pintype "passive"))
      (node (ref "JP10") (pin "3") (pinfunction "3_3") (pintype "passive"))
      (node (ref "JP11") (pin "1") (pinfunction "1_1") (pintype "passive"))
      (node (ref "JP12") (pin "3") (pinfunction "3_3") (pintype "passive"))
      (node (ref "JP14") (pin "1") (pinfunction "1_1") (pintype "passive"))
      (node (ref "JP15") (pin "2") (pinfunction "2_2") (pintype "passive"))
      (node (ref "JP16") (pin "2") (pinfunction "2_2") (pintype "passive"))
      (node (ref "JP4") (pin "1") (pinfunction "1_1") (pintype "passive"))
      (node (ref "JP7") (pin "3") (pinfunction "3_3") (pintype "passive"))
      (node (ref "JP8") (pin "3") (pinfunction "3_3") (pintype "passive"))
      (node (ref "LED1") (pin "C") (pinfunction "C_C") (pintype "passive"))
      (node (ref "Q1") (pin "3") (pinfunction "S_3") (pintype "passive"))
      (node (ref "Q2") (pin "3") (pinfunction "S_3") (pintype "passive"))
      (node (ref "Q3") (pin "2") (pinfunction "S_2") (pintype "passive"))
      (node (ref "Q4") (pin "2") (pinfunction "S_2") (pintype "passive"))
      (node (ref "Q5") (pin "2") (pinfunction "S_2") (pintype "passive"))
      (node (ref "Q6") (pin "2") (pinfunction "S_2") (pintype "passive"))
      (node (ref "Q7") (pin "2") (pinfunction "S_2") (pintype "passive"))
      (node (ref "R14") (pin "2") (pinfunction "2_2") (pintype "passive"))
      (node (ref "R16") (pin "2") (pinfunction "2_2") (pintype "passive"))
      (node (ref "R17") (pin "2") (pinfunction "2_2") (pintype "passive"))
      (node (ref "R18") (pin "2") (pinfunction "2_2") (pintype "passive"))
      (node (ref "R19") (pin "2") (pinfunction "2_2") (pintype "passive"))
      (node (ref "R2") (pin "2") (pinfunction "2_2") (pintype "passive"))
      (node (ref "R20") (pin "2") (pinfunction "2_2") (pintype "passive"))
      (node (ref "R23") (pin "2") (pinfunction "2_2") (pintype "passive"))
      (node (ref "R24") (pin "2") (pinfunction "2_2") (pintype "passive"))
      (node (ref "R25") (pin "2") (pinfunction "2_2") (pintype "passive"))
      (node (ref "R26") (pin "2") (pinfunction "2_2") (pintype "passive"))
      (node (ref "R29") (pin "2") (pinfunction "2_2") (pintype "passive"))
      (node (ref "R30") (pin "2") (pinfunction "2_2") (pintype "passive"))
      (node (ref "R31") (pin "2") (pinfunction "2_2") (pintype "passive"))
      (node (ref "R32") (pin "2") (pinfunction "2_2") (pintype "passive"))
      (node (ref "R35") (pin "2") (pinfunction "2_2") (pintype "passive"))
      (node (ref "R38") (pin "2") (pinfunction "2_2") (pintype "passive"))
      (node (ref "R39") (pin "2") (pinfunction "2_2") (pintype "passive"))
      (node (ref "R40") (pin "2") (pinfunction "2_2") (pintype "passive"))
      (node (ref "R6") (pin "2") (pinfunction "2_2") (pintype "passive"))
      (node (ref "S1") (pin "B2") (pinfunction "2_B2") (pintype "passive"))
      (node (ref "U1") (pin "2") (pinfunction "GND_2") (pintype "power_in"))
      (node (ref "U10") (pin "10") (pinfunction "VSS_10") (pintype "power_in"))
      (node (ref "U2") (pin "13") (pinfunction "GND1_13") (pintype "power_in"))
      (node (ref "U2") (pin "24") (pinfunction "GND2_24") (pintype "power_in"))
      (node (ref "U2") (pin "PAD") (pinfunction "PAD_PAD") (pintype "power_in"))
      (node (ref "U3") (pin "13") (pinfunction "GND1_13") (pintype "power_in"))
      (node (ref "U3") (pin "24") (pinfunction "GND2_24") (pintype "power_in"))
      (node (ref "U3") (pin "PAD") (pinfunction "PAD_PAD") (pintype "power_in"))
      (node (ref "U4") (pin "13") (pinfunction "GND1_13") (pintype "power_in"))
      (node (ref "U4") (pin "24") (pinfunction "GND2_24") (pintype "power_in"))
      (node (ref "U4") (pin "PAD") (pinfunction "PAD_PAD") (pintype "power_in"))
      (node (ref "U5") (pin "13") (pinfunction "GND1_13") (pintype "power_in"))
      (node (ref "U5") (pin "24") (pinfunction "GND2_24") (pintype "power_in"))
      (node (ref "U5") (pin "PAD") (pinfunction "PAD_PAD") (pintype "power_in"))
      (node (ref "U6") (pin "22") (pinfunction "GND_22") (pintype "power_in"))
      (node (ref "U6") (pin "53") (pinfunction "GND_53") (pintype "power_in"))
      (node (ref "U6") (pin "6") (pinfunction "UGND_6") (pintype "power_in"))
      (node (ref "U6") (pin "63") (pinfunction "AGND_63") (pintype "power_in"))
      (node (ref "U7") (pin "3") (pinfunction "GND_3") (pintype "power_in"))
      (node (ref "U8") (pin "7") (pinfunction "GND_7") (pintype "power_in"))
      (node (ref "U9") (pin "2") (pinfunction "GND_2") (pintype "power_in"))
    )
    (net (code "69") (name "Net-(D-SUB-Pad1)") (class "Default")
      (node (ref "D-SUB") (pin "1") (pinfunction "1_1") (pintype "bidirectional"))
      (node (ref "R41") (pin "2") (pinfunction "2_2") (pintype "passive"))
    )
    (net (code "70") (name "Net-(D-SUB-Pad2)") (class "Default")
      (node (ref "D-SUB") (pin "2") (pinfunction "2_2") (pintype "bidirectional"))
      (node (ref "R42") (pin "2") (pinfunction "2_2") (pintype "passive"))
    )
    (net (code "71") (name "Net-(D-SUB-Pad3)") (class "Default")
      (node (ref "D-SUB") (pin "3") (pinfunction "3_3") (pintype "bidirectional"))
      (node (ref "R43") (pin "2") (pinfunction "2_2") (pintype "passive"))
    )
    (net (code "72") (name "Net-(D-SUB-Pad4)") (class "Default")
      (node (ref "D-SUB") (pin "4") (pinfunction "4_4") (pintype "bidirectional"))
      (node (ref "R44") (pin "2") (pinfunction "2_2") (pintype "passive"))
    )
    (net (code "73") (name "Net-(D-SUB-Pad5)") (class "Default")
      (node (ref "D-SUB") (pin "5") (pinfunction "5_5") (pintype "bidirectional"))
      (node (ref "R45") (pin "2") (pinfunction "2_2") (pintype "passive"))
    )
    (net (code "74") (name "Net-(J2C-S)") (class "Default")
      (node (ref "J2") (pin "3") (pinfunction "S_3") (pintype "passive"))
      (node (ref "J2") (pin "4") (pinfunction "S_4") (pintype "passive"))
      (node (ref "Q2") (pin "2") (pinfunction "D_2") (pintype "passive"))
    )
    (net (code "75") (name "Net-(L1-1)") (class "Default")
      (node (ref "C2") (pin "1") (pinfunction "1_1") (pintype "passive"))
      (node (ref "D1") (pin "C") (pinfunction "C_C") (pintype "passive"))
      (node (ref "L1") (pin "P$1") (pinfunction "1_P$1") (pintype "passive"))
      (node (ref "U1") (pin "6") (pinfunction "SW_6") (pintype "passive"))
    )
    (net (code "76") (name "Net-(LED1-PadA)") (class "Default")
      (node (ref "LED1") (pin "A") (pinfunction "A_A") (pintype "passive"))
      (node (ref "R1") (pin "1") (pinfunction "1_1") (pintype "passive"))
    )
    (net (code "77") (name "Net-(Q1-D)") (class "Default")
      (node (ref "JP6") (pin "1") (pinfunction "1_1") (pintype "passive"))
      (node (ref "JP6") (pin "2") (pinfunction "2_2") (pintype "passive"))
      (node (ref "Q1") (pin "2") (pinfunction "D_2") (pintype "passive"))
    )
    (net (code "78") (name "Net-(Q1-G)") (class "Default")
      (node (ref "Q1") (pin "1") (pinfunction "G_1") (pintype "passive"))
      (node (ref "R36") (pin "2") (pinfunction "2_2") (pintype "passive"))
    )
    (net (code "79") (name "Net-(Q2-G)") (class "Default")
      (node (ref "Q2") (pin "1") (pinfunction "G_1") (pintype "passive"))
      (node (ref "R11") (pin "2") (pinfunction "2_2") (pintype "passive"))
    )
    (net (code "80") (name "Net-(Q3-D)") (class "Default")
      (node (ref "D2") (pin "C") (pinfunction "C_C") (pintype "passive"))
      (node (ref "FAN") (pin "2") (pinfunction "2_2") (pintype "passive"))
      (node (ref "Q3") (pin "3") (pinfunction "D_3") (pintype "passive"))
    )
    (net (code "81") (name "Net-(Q4-D)") (class "Default")
      (node (ref "D3") (pin "C") (pinfunction "C_C") (pintype "passive"))
      (node (ref "FAN") (pin "3") (pinfunction "3_3") (pintype "passive"))
      (node (ref "Q4") (pin "3") (pinfunction "D_3") (pintype "passive"))
    )
    (net (code "82") (name "Net-(Q5-D)") (class "Default")
      (node (ref "D4") (pin "C") (pinfunction "C_C") (pintype "passive"))
      (node (ref "FAN") (pin "4") (pinfunction "4_4") (pintype "passive"))
      (node (ref "Q5") (pin "3") (pinfunction "D_3") (pintype "passive"))
    )
    (net (code "83") (name "Net-(Q6-D)") (class "Default")
      (node (ref "BLUE-LED") (pin "2") (pinfunction "2_2") (pintype "passive"))
      (node (ref "D5") (pin "C") (pinfunction "C_C") (pintype "passive"))
      (node (ref "Q6") (pin "3") (pinfunction "D_3") (pintype "passive"))
    )
    (net (code "84") (name "Net-(Q7-D)") (class "Default")
      (node (ref "D6") (pin "C") (pinfunction "C_C") (pintype "passive"))
      (node (ref "Q7") (pin "3") (pinfunction "D_3") (pintype "passive"))
      (node (ref "RED-LED") (pin "2") (pinfunction "2_2") (pintype "passive"))
    )
    (net (code "85") (name "Net-(U1-CB)") (class "Default")
      (node (ref "C2") (pin "2") (pinfunction "2_2") (pintype "passive"))
      (node (ref "U1") (pin "1") (pinfunction "CB_1") (pintype "passive"))
    )
    (net (code "86") (name "Net-(U1-FB)") (class "Default")
      (node (ref "R37") (pin "2") (pinfunction "2_2") (pintype "passive"))
      (node (ref "R38") (pin "1") (pinfunction "1_1") (pintype "passive"))
      (node (ref "U1") (pin "3") (pinfunction "FB_3") (pintype "passive"))
    )
    (net (code "87") (name "Net-(U2-CP1)") (class "Default")
      (node (ref "C5") (pin "2") (pinfunction "2_2") (pintype "passive"))
      (node (ref "U2") (pin "1") (pinfunction "CP1_1") (pintype "passive"))
    )
    (net (code "88") (name "Net-(U2-CP2)") (class "Default")
      (node (ref "C5") (pin "1") (pinfunction "1_1") (pintype "passive"))
      (node (ref "U2") (pin "2") (pinfunction "CP2_2") (pintype "passive"))
    )
    (net (code "89") (name "Net-(U2-MS1)") (class "Default")
      (node (ref "MS-X") (pin "1") (pinfunction "1_1") (pintype "passive"))
      (node (ref "U2") (pin "5") (pinfunction "MS1_5") (pintype "input"))
    )
    (net (code "90") (name "Net-(U2-MS2)") (class "Default")
      (node (ref "MS-X") (pin "3") (pinfunction "3_3") (pintype "passive"))
      (node (ref "U2") (pin "6") (pinfunction "MS2_6") (pintype "input"))
    )
    (net (code "91") (name "Net-(U2-OUT1A)") (class "Default")
      (node (ref "JP9") (pin "3") (pinfunction "3_3") (pintype "passive"))
      (node (ref "U2") (pin "18") (pinfunction "OUT1A_18") (pintype "output"))
    )
    (net (code "92") (name "Net-(U2-OUT1B)") (class "Default")
      (node (ref "JP9") (pin "4") (pinfunction "4_4") (pintype "passive"))
      (node (ref "U2") (pin "15") (pinfunction "OUT1B_15") (pintype "output"))
    )
    (net (code "93") (name "Net-(U2-OUT2A)") (class "Default")
      (node (ref "JP9") (pin "2") (pinfunction "2_2") (pintype "passive"))
      (node (ref "U2") (pin "19") (pinfunction "OUT2A_19") (pintype "output"))
    )
    (net (code "94") (name "Net-(U2-OUT2B)") (class "Default")
      (node (ref "JP9") (pin "1") (pinfunction "1_1") (pintype "passive"))
      (node (ref "U2") (pin "22") (pinfunction "OUT2B_22") (pintype "output"))
    )
    (net (code "95") (name "Net-(U2-ROSC)") (class "Default")
      (node (ref "R2") (pin "1") (pinfunction "1_1") (pintype "passive"))
      (node (ref "U2") (pin "8") (pinfunction "ROSC_8") (pintype "passive"))
    )
    (net (code "96") (name "Net-(U2-SENSE1)") (class "Default")
      (node (ref "R17") (pin "1") (pinfunction "1_1") (pintype "passive"))
      (node (ref "U2") (pin "17") (pinfunction "SENSE1_17") (pintype "passive"))
    )
    (net (code "97") (name "Net-(U2-SENSE2)") (class "Default")
      (node (ref "R18") (pin "1") (pinfunction "1_1") (pintype "passive"))
      (node (ref "U2") (pin "20") (pinfunction "SENSE2_20") (pintype "passive"))
    )
    (net (code "98") (name "Net-(U2-VCP)") (class "Default")
      (node (ref "C4") (pin "2") (pinfunction "2_2") (pintype "passive"))
      (node (ref "U2") (pin "3") (pinfunction "VCP_3") (pintype "passive"))
    )
    (net (code "99") (name "Net-(U2-VREG)") (class "Default")
      (node (ref "C8") (pin "2") (pinfunction "2_2") (pintype "passive"))
      (node (ref "U2") (pin "4") (pinfunction "VREG_4") (pintype "passive"))
    )
    (net (code "100") (name "Net-(U2-~{RESET})") (class "Default")
      (node (ref "R4") (pin "2") (pinfunction "2_2") (pintype "passive"))
      (node (ref "U2") (pin "7") (pinfunction "~{RESET}_7") (pintype "input"))
      (node (ref "U2") (pin "9") (pinfunction "~{SLEEP}_9") (pintype "input"))
    )
    (net (code "101") (name "Net-(U3-CP1)") (class "Default")
      (node (ref "C17") (pin "2") (pinfunction "2_2") (pintype "passive"))
      (node (ref "U3") (pin "1") (pinfunction "CP1_1") (pintype "passive"))
    )
    (net (code "102") (name "Net-(U3-CP2)") (class "Default")
      (node (ref "C17") (pin "1") (pinfunction "1_1") (pintype "passive"))
      (node (ref "U3") (pin "2") (pinfunction "CP2_2") (pintype "passive"))
    )
    (net (code "103") (name "Net-(U3-MS1)") (class "Default")
      (node (ref "MS-Y") (pin "1") (pinfunction "1_1") (pintype "passive"))
      (node (ref "U3") (pin "5") (pinfunction "MS1_5") (pintype "input"))
    )
    (net (code "104") (name "Net-(U3-MS2)") (class "Default")
      (node (ref "MS-Y") (pin "3") (pinfunction "3_3") (pintype "passive"))
      (node (ref "U3") (pin "6") (pinfunction "MS2_6") (pintype "input"))
    )
    (net (code "105") (name "Net-(U3-OUT1A)") (class "Default")
      (node (ref "JP1") (pin "3") (pinfunction "3_3") (pintype "passive"))
      (node (ref "U3") (pin "18") (pinfunction "OUT1A_18") (pintype "output"))
    )
    (net (code "106") (name "Net-(U3-OUT1B)") (class "Default")
      (node (ref "JP1") (pin "4") (pinfunction "4_4") (pintype "passive"))
      (node (ref "U3") (pin "15") (pinfunction "OUT1B_15") (pintype "output"))
    )
    (net (code "107") (name "Net-(U3-OUT2A)") (class "Default")
      (node (ref "JP1") (pin "2") (pinfunction "2_2") (pintype "passive"))
      (node (ref "U3") (pin "19") (pinfunction "OUT2A_19") (pintype "output"))
    )
    (net (code "108") (name "Net-(U3-OUT2B)") (class "Default")
      (node (ref "JP1") (pin "1") (pinfunction "1_1") (pintype "passive"))
      (node (ref "U3") (pin "22") (pinfunction "OUT2B_22") (pintype "output"))
    )
    (net (code "109") (name "Net-(U3-ROSC)") (class "Default")
      (node (ref "R20") (pin "1") (pinfunction "1_1") (pintype "passive"))
      (node (ref "U3") (pin "8") (pinfunction "ROSC_8") (pintype "passive"))
    )
    (net (code "110") (name "Net-(U3-SENSE1)") (class "Default")
      (node (ref "R16") (pin "1") (pinfunction "1_1") (pintype "passive"))
      (node (ref "U3") (pin "17") (pinfunction "SENSE1_17") (pintype "passive"))
    )
    (net (code "111") (name "Net-(U3-SENSE2)") (class "Default")
      (node (ref "R19") (pin "1") (pinfunction "1_1") (pintype "passive"))
      (node (ref "U3") (pin "20") (pinfunction "SENSE2_20") (pintype "passive"))
    )
    (net (code "112") (name "Net-(U3-VCP)") (class "Default")
      (node (ref "C21") (pin "2") (pinfunction "2_2") (pintype "passive"))
      (node (ref "U3") (pin "3") (pinfunction "VCP_3") (pintype "passive"))
    )
    (net (code "113") (name "Net-(U3-VREG)") (class "Default")
      (node (ref "C19") (pin "2") (pinfunction "2_2") (pintype "passive"))
      (node (ref "U3") (pin "4") (pinfunction "VREG_4") (pintype "passive"))
    )
    (net (code "114") (name "Net-(U3-~{RESET})") (class "Default")
      (node (ref "R22") (pin "2") (pinfunction "2_2") (pintype "passive"))
      (node (ref "U3") (pin "7") (pinfunction "~{RESET}_7") (pintype "input"))
      (node (ref "U3") (pin "9") (pinfunction "~{SLEEP}_9") (pintype "input"))
    )
    (net (code "115") (name "Net-(U4-CP1)") (class "Default")
      (node (ref "C22") (pin "2") (pinfunction "2_2") (pintype "passive"))
      (node (ref "U4") (pin "1") (pinfunction "CP1_1") (pintype "passive"))
    )
    (net (code "116") (name "Net-(U4-CP2)") (class "Default")
      (node (ref "C22") (pin "1") (pinfunction "1_1") (pintype "passive"))
      (node (ref "U4") (pin "2") (pinfunction "CP2_2") (pintype "passive"))
    )
    (net (code "117") (name "Net-(U4-MS1)") (class "Default")
      (node (ref "MS-Z") (pin "1") (pinfunction "1_1") (pintype "passive"))
      (node (ref "U4") (pin "5") (pinfunction "MS1_5") (pintype "input"))
    )
    (net (code "118") (name "Net-(U4-MS2)") (class "Default")
      (node (ref "MS-Z") (pin "3") (pinfunction "3_3") (pintype "passive"))
      (node (ref "U4") (pin "6") (pinfunction "MS2_6") (pintype "input"))
    )
    (net (code "119") (name "Net-(U4-OUT1A)") (class "Default")
      (node (ref "JP3") (pin "3") (pinfunction "3_3") (pintype "passive"))
      (node (ref "U4") (pin "18") (pinfunction "OUT1A_18") (pintype "output"))
    )
    (net (code "120") (name "Net-(U4-OUT1B)") (class "Default")
      (node (ref "JP3") (pin "4") (pinfunction "4_4") (pintype "passive"))
      (node (ref "U4") (pin "15") (pinfunction "OUT1B_15") (pintype "output"))
    )
    (net (code "121") (name "Net-(U4-OUT2A)") (class "Default")
      (node (ref "JP3") (pin "2") (pinfunction "2_2") (pintype "passive"))
      (node (ref "U4") (pin "19") (pinfunction "OUT2A_19") (pintype "output"))
    )
    (net (code "122") (name "Net-(U4-OUT2B)") (class "Default")
      (node (ref "JP3") (pin "1") (pinfunction "1_1") (pintype "passive"))
      (node (ref "U4") (pin "22") (pinfunction "OUT2B_22") (pintype "output"))
    )
    (net (code "123") (name "Net-(U4-ROSC)") (class "Default")
      (node (ref "R26") (pin "1") (pinfunction "1_1") (pintype "passive"))
      (node (ref "U4") (pin "8") (pinfunction "ROSC_8") (pintype "passive"))
    )
    (net (code "124") (name "Net-(U4-SENSE1)") (class "Default")
      (node (ref "R24") (pin "1") (pinfunction "1_1") (pintype "passive"))
      (node (ref "U4") (pin "17") (pinfunction "SENSE1_17") (pintype "passive"))
    )
    (net (code "125") (name "Net-(U4-SENSE2)") (class "Default")
      (node (ref "R25") (pin "1") (pinfunction "1_1") (pintype "passive"))
      (node (ref "U4") (pin "20") (pinfunction "SENSE2_20") (pintype "passive"))
    )
    (net (code "126") (name "Net-(U4-VCP)") (class "Default")
      (node (ref "C26") (pin "2") (pinfunction "2_2") (pintype "passive"))
      (node (ref "U4") (pin "3") (pinfunction "VCP_3") (pintype "passive"))
    )
    (net (code "127") (name "Net-(U4-VREG)") (class "Default")
      (node (ref "C24") (pin "2") (pinfunction "2_2") (pintype "passive"))
      (node (ref "U4") (pin "4") (pinfunction "VREG_4") (pintype "passive"))
    )
    (net (code "128") (name "Net-(U4-~{RESET})") (class "Default")
      (node (ref "R28") (pin "2") (pinfunction "2_2") (pintype "passive"))
      (node (ref "U4") (pin "7") (pinfunction "~{RESET}_7") (pintype "input"))
      (node (ref "U4") (pin "9") (pinfunction "~{SLEEP}_9") (pintype "input"))
    )
    (net (code "129") (name "Net-(U5-CP1)") (class "Default")
      (node (ref "C27") (pin "2") (pinfunction "2_2") (pintype "passive"))
      (node (ref "U5") (pin "1") (pinfunction "CP1_1") (pintype "passive"))
    )
    (net (code "130") (name "Net-(U5-CP2)") (class "Default")
      (node (ref "C27") (pin "1") (pinfunction "1_1") (pintype "passive"))
      (node (ref "U5") (pin "2") (pinfunction "CP2_2") (pintype "passive"))
    )
    (net (code "131") (name "Net-(U5-MS1)") (class "Default")
      (node (ref "MS-E") (pin "1") (pinfunction "1_1") (pintype "passive"))
      (node (ref "U5") (pin "5") (pinfunction "MS1_5") (pintype "input"))
    )
    (net (code "132") (name "Net-(U5-MS2)") (class "Default")
      (node (ref "MS-E") (pin "3") (pinfunction "3_3") (pintype "passive"))
      (node (ref "U5") (pin "6") (pinfunction "MS2_6") (pintype "input"))
    )
    (net (code "133") (name "Net-(U5-OUT1A)") (class "Default")
      (node (ref "JP5") (pin "3") (pinfunction "3_3") (pintype "passive"))
      (node (ref "U5") (pin "18") (pinfunction "OUT1A_18") (pintype "output"))
    )
    (net (code "134") (name "Net-(U5-OUT1B)") (class "Default")
      (node (ref "JP5") (pin "4") (pinfunction "4_4") (pintype "passive"))
      (node (ref "U5") (pin "15") (pinfunction "OUT1B_15") (pintype "output"))
    )
    (net (code "135") (name "Net-(U5-OUT2A)") (class "Default")
      (node (ref "JP5") (pin "2") (pinfunction "2_2") (pintype "passive"))
      (node (ref "U5") (pin "19") (pinfunction "OUT2A_19") (pintype "output"))
    )
    (net (code "136") (name "Net-(U5-OUT2B)") (class "Default")
      (node (ref "JP5") (pin "1") (pinfunction "1_1") (pintype "passive"))
      (node (ref "U5") (pin "22") (pinfunction "OUT2B_22") (pintype "output"))
    )
    (net (code "137") (name "Net-(U5-ROSC)") (class "Default")
      (node (ref "R32") (pin "1") (pinfunction "1_1") (pintype "passive"))
      (node (ref "U5") (pin "8") (pinfunction "ROSC_8") (pintype "passive"))
    )
    (net (code "138") (name "Net-(U5-SENSE1)") (class "Default")
      (node (ref "R30") (pin "1") (pinfunction "1_1") (pintype "passive"))
      (node (ref "U5") (pin "17") (pinfunction "SENSE1_17") (pintype "passive"))
    )
    (net (code "139") (name "Net-(U5-SENSE2)") (class "Default")
      (node (ref "R31") (pin "1") (pinfunction "1_1") (pintype "passive"))
      (node (ref "U5") (pin "20") (pinfunction "SENSE2_20") (pintype "passive"))
    )
    (net (code "140") (name "Net-(U5-VCP)") (class "Default")
      (node (ref "C31") (pin "2") (pinfunction "2_2") (pintype "passive"))
      (node (ref "U5") (pin "3") (pinfunction "VCP_3") (pintype "passive"))
    )
    (net (code "141") (name "Net-(U5-VREG)") (class "Default")
      (node (ref "C29") (pin "2") (pinfunction "2_2") (pintype "passive"))
      (node (ref "U5") (pin "4") (pinfunction "VREG_4") (pintype "passive"))
    )
    (net (code "142") (name "Net-(U5-~{RESET})") (class "Default")
      (node (ref "R34") (pin "2") (pinfunction "2_2") (pintype "passive"))
      (node (ref "U5") (pin "7") (pinfunction "~{RESET}_7") (pintype "input"))
      (node (ref "U5") (pin "9") (pinfunction "~{SLEEP}_9") (pintype "input"))
    )
    (net (code "143") (name "Net-(U6-AREF)") (class "Default")
      (node (ref "C3") (pin "1") (pinfunction "1_1") (pintype "passive"))
      (node (ref "U6") (pin "62") (pinfunction "AREF_62") (pintype "power_in"))
    )
    (net (code "144") (name "Net-(U6-D+)") (class "Default")
      (node (ref "R8") (pin "2") (pinfunction "2_2") (pintype "passive"))
      (node (ref "U6") (pin "5") (pinfunction "D+_5") (pintype "bidirectional"))
    )
    (net (code "145") (name "Net-(U6-D-)") (class "Default")
      (node (ref "R7") (pin "2") (pinfunction "2_2") (pintype "passive"))
      (node (ref "U6") (pin "4") (pinfunction "D-_4") (pintype "bidirectional"))
    )
    (net (code "146") (name "Net-(U6-UCAP)") (class "Default")
      (node (ref "C11") (pin "2") (pinfunction "2_2") (pintype "passive"))
      (node (ref "U6") (pin "7") (pinfunction "UCAP_7") (pintype "power_in"))
    )
    (net (code "147") (name "unconnected-(J1-DAT1-Pad8)") (class "Default")
      (node (ref "J1") (pin "8") (pinfunction "DAT1_8") (pintype "bidirectional"))
    )
    (net (code "148") (name "unconnected-(J1-DAT2-Pad9)") (class "Default")
      (node (ref "J1") (pin "9") (pinfunction "DAT2_9") (pintype "bidirectional"))
    )
    (net (code "149") (name "unconnected-(J1-PadSA)") (class "Default")
      (node (ref "J1") (pin "SA") (pinfunction "SA_SA") (pintype "bidirectional"))
    )
    (net (code "150") (name "unconnected-(U9-IO3-Pad4)") (class "Default")
      (node (ref "U9") (pin "4") (pinfunction "IO3_4") (pintype "bidirectional"))
    )
    (net (code "151") (name "unconnected-(U9-IO4-Pad6)") (class "Default")
      (node (ref "U9") (pin "6") (pinfunction "IO4_6") (pintype "bidirectional"))
    )
    (net (code "152") (name "unconnected-(U10-RDY{slash}~{BSY}-Pad5)") (class "Default")
      (node (ref "U10") (pin "5") (pinfunction "RDY/~{BSY}_5") (pintype "input"))
    )
  )
)
